# SCH_MyFirstCPU_2022-09-18.net
KiCad netlist of a schematic drawn in EasyEDA
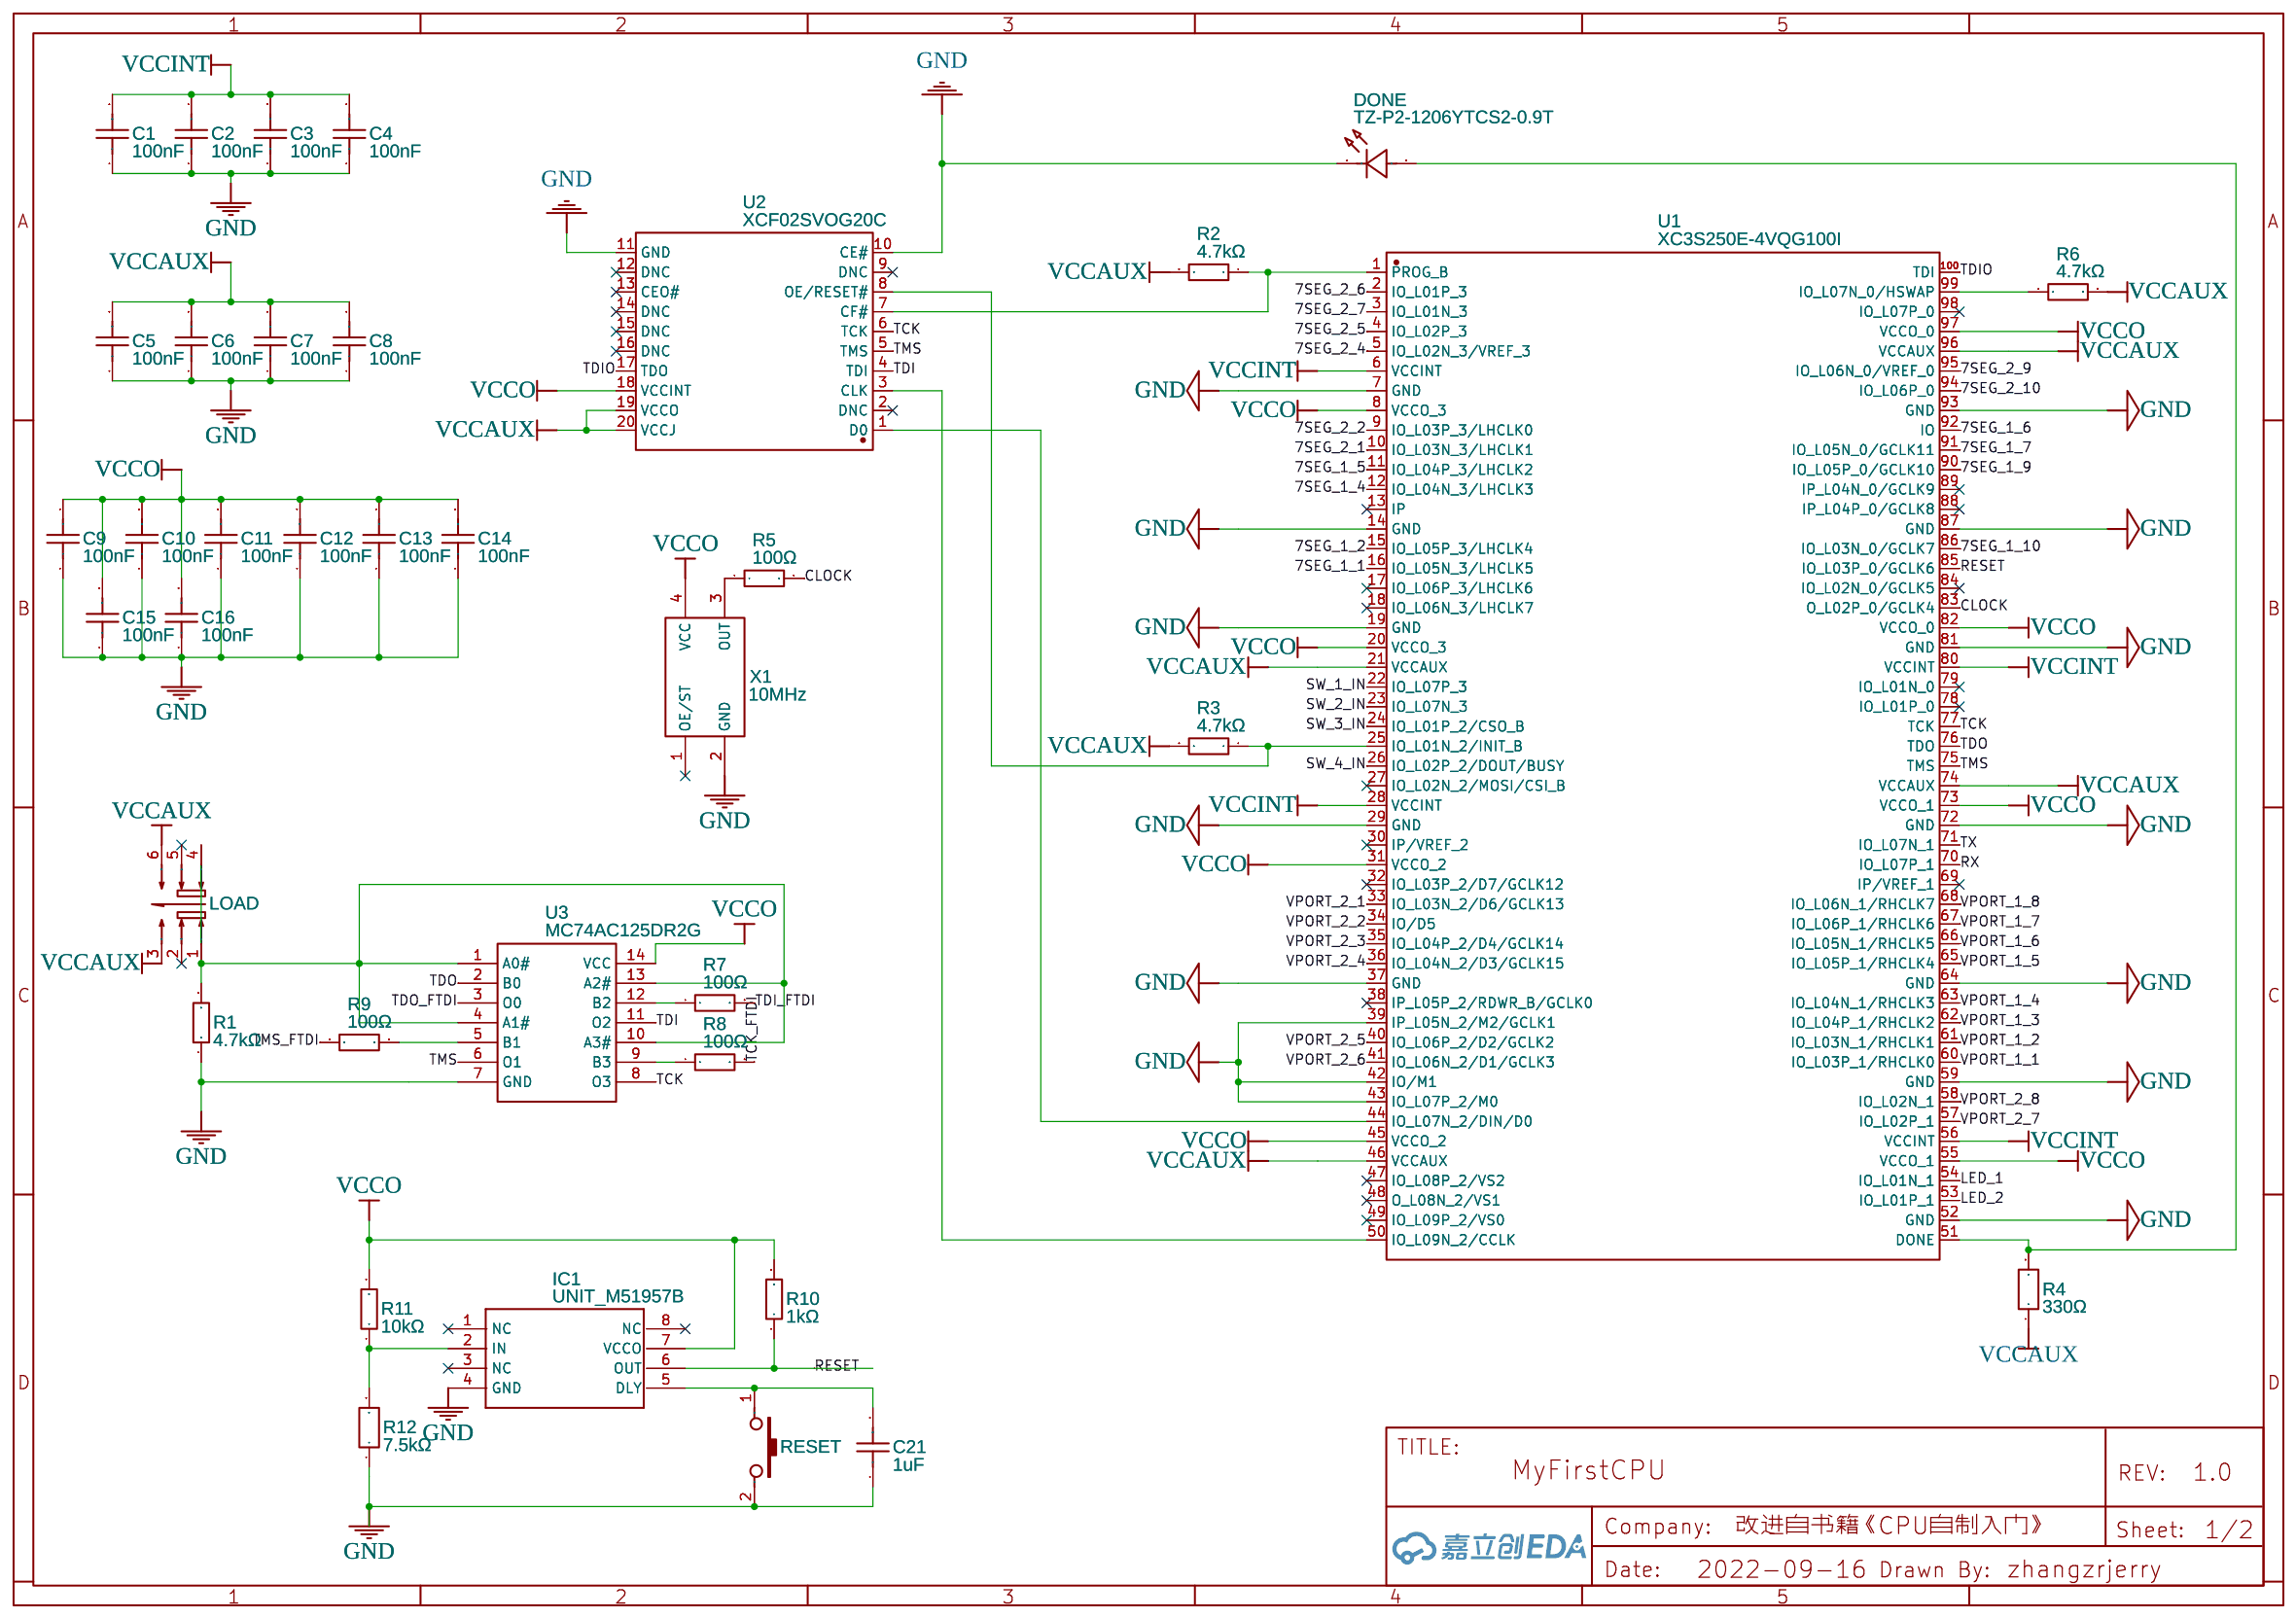
[diagram p0: Sheet_1]
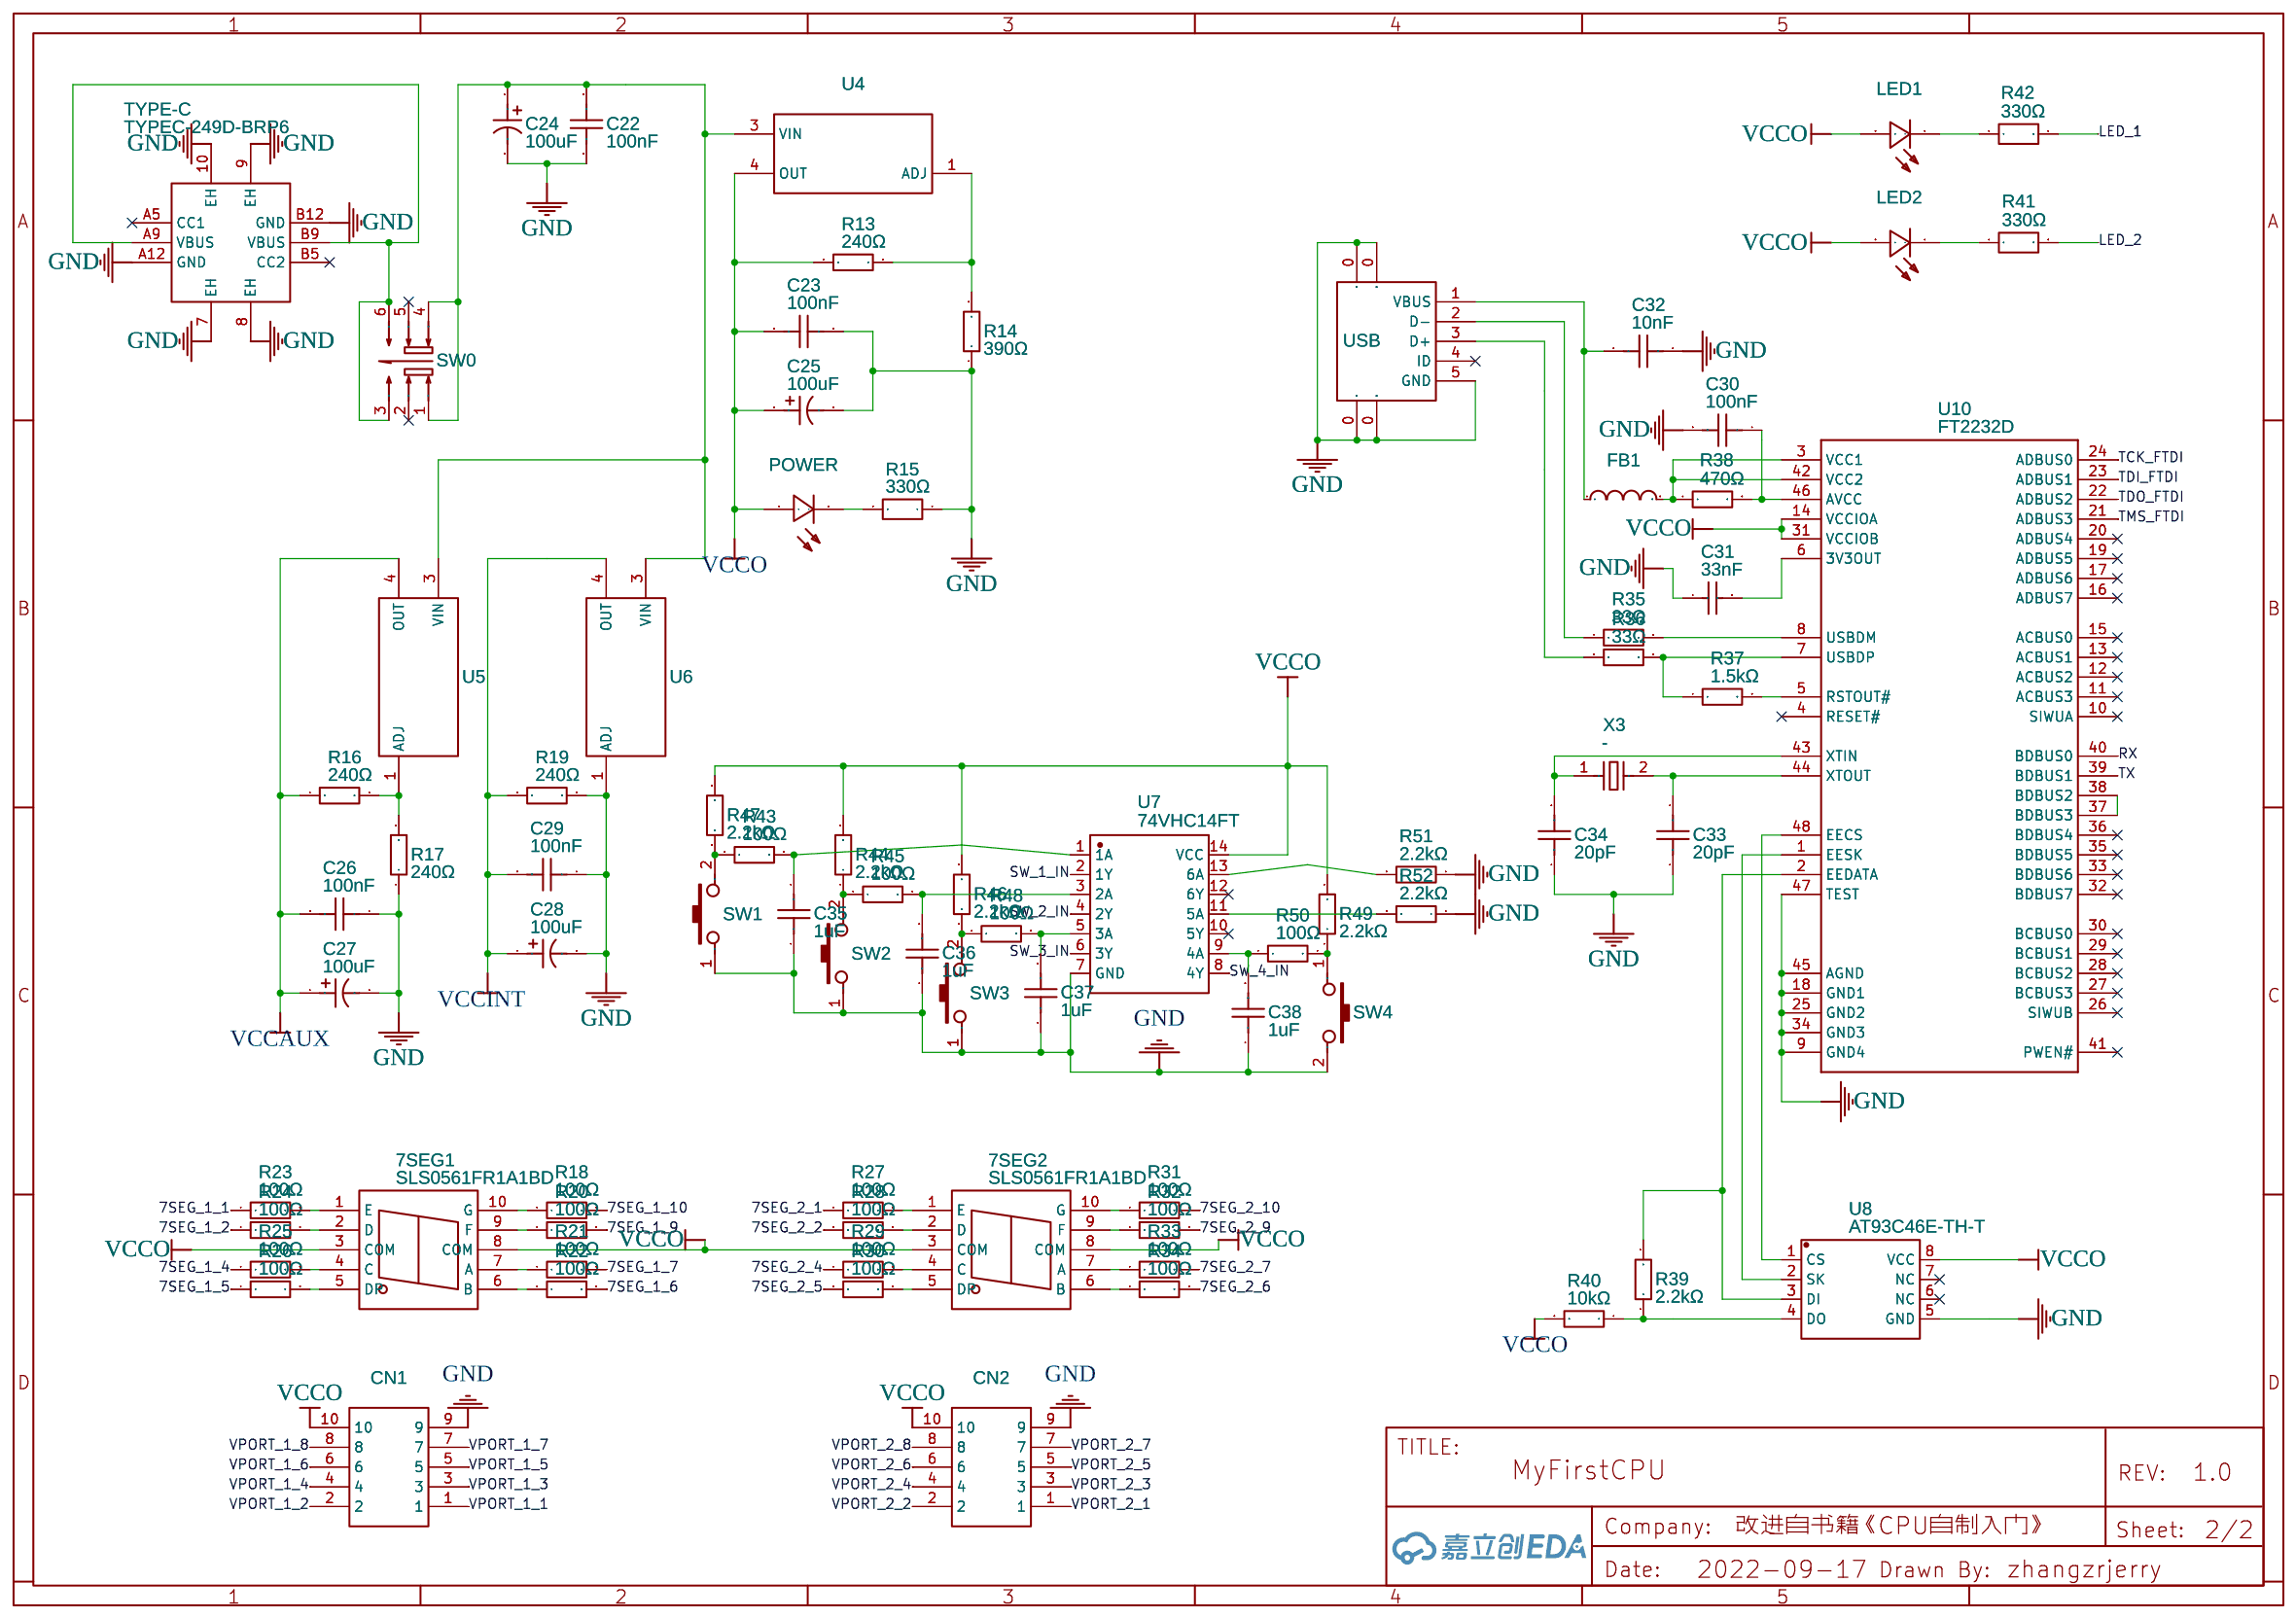
[diagram p1: Sheet_2]

(export (version "E")
  (design (tool "Eeschema 10.0.6"))
  (components
    (comp (ref "C1")
      (value "100nF")
      (fields
        (field (name "BOM_Manufacturer Part") "GRM31MR71H104KA01L")
        (field (name "BOM_Supplier Part") "C469550")
      )
      (libsource (lib "") (part "GRM31MR71H104KA01L"))
    )
    (comp (ref "C2")
      (value "100nF")
      (fields
        (field (name "BOM_Manufacturer Part") "GRM31MR71H104KA01L")
        (field (name "BOM_Supplier Part") "C469550")
      )
      (libsource (lib "") (part "GRM31MR71H104KA01L"))
    )
    (comp (ref "C3")
      (value "100nF")
      (fields
        (field (name "BOM_Manufacturer Part") "GRM31MR71H104KA01L")
        (field (name "BOM_Supplier Part") "C469550")
      )
      (libsource (lib "") (part "GRM31MR71H104KA01L"))
    )
    (comp (ref "C4")
      (value "100nF")
      (fields
        (field (name "BOM_Manufacturer Part") "GRM31MR71H104KA01L")
        (field (name "BOM_Supplier Part") "C469550")
      )
      (libsource (lib "") (part "GRM31MR71H104KA01L"))
    )
    (comp (ref "C5")
      (value "100nF")
      (fields
        (field (name "BOM_Manufacturer Part") "GRM31MR71H104KA01L")
        (field (name "BOM_Supplier Part") "C469550")
      )
      (libsource (lib "") (part "GRM31MR71H104KA01L"))
    )
    (comp (ref "C6")
      (value "100nF")
      (fields
        (field (name "BOM_Manufacturer Part") "GRM31MR71H104KA01L")
        (field (name "BOM_Supplier Part") "C469550")
      )
      (libsource (lib "") (part "GRM31MR71H104KA01L"))
    )
    (comp (ref "C7")
      (value "100nF")
      (fields
        (field (name "BOM_Manufacturer Part") "GRM31MR71H104KA01L")
        (field (name "BOM_Supplier Part") "C469550")
      )
      (libsource (lib "") (part "GRM31MR71H104KA01L"))
    )
    (comp (ref "C8")
      (value "100nF")
      (fields
        (field (name "BOM_Manufacturer Part") "GRM31MR71H104KA01L")
        (field (name "BOM_Supplier Part") "C469550")
      )
      (libsource (lib "") (part "GRM31MR71H104KA01L"))
    )
    (comp (ref "C9")
      (value "100nF")
      (fields
        (field (name "BOM_Manufacturer Part") "GRM31MR71H104KA01L")
        (field (name "BOM_Supplier Part") "C469550")
      )
      (libsource (lib "") (part "GRM31MR71H104KA01L"))
    )
    (comp (ref "C10")
      (value "100nF")
      (fields
        (field (name "BOM_Manufacturer Part") "GRM31MR71H104KA01L")
        (field (name "BOM_Supplier Part") "C469550")
      )
      (libsource (lib "") (part "GRM31MR71H104KA01L"))
    )
    (comp (ref "C11")
      (value "100nF")
      (fields
        (field (name "BOM_Manufacturer Part") "GRM31MR71H104KA01L")
        (field (name "BOM_Supplier Part") "C469550")
      )
      (libsource (lib "") (part "GRM31MR71H104KA01L"))
    )
    (comp (ref "C12")
      (value "100nF")
      (fields
        (field (name "BOM_Manufacturer Part") "GRM31MR71H104KA01L")
        (field (name "BOM_Supplier Part") "C469550")
      )
      (libsource (lib "") (part "GRM31MR71H104KA01L"))
    )
    (comp (ref "C13")
      (value "100nF")
      (fields
        (field (name "BOM_Manufacturer Part") "GRM31MR71H104KA01L")
        (field (name "BOM_Supplier Part") "C469550")
      )
      (libsource (lib "") (part "GRM31MR71H104KA01L"))
    )
    (comp (ref "C14")
      (value "100nF")
      (fields
        (field (name "BOM_Manufacturer Part") "GRM31MR71H104KA01L")
        (field (name "BOM_Supplier Part") "C469550")
      )
      (libsource (lib "") (part "GRM31MR71H104KA01L"))
    )
    (comp (ref "C15")
      (value "100nF")
      (fields
        (field (name "BOM_Manufacturer Part") "GRM31MR71H104KA01L")
        (field (name "BOM_Supplier Part") "C469550")
      )
      (libsource (lib "") (part "GRM31MR71H104KA01L"))
    )
    (comp (ref "C16")
      (value "100nF")
      (fields
        (field (name "BOM_Manufacturer Part") "GRM31MR71H104KA01L")
        (field (name "BOM_Supplier Part") "C469550")
      )
      (libsource (lib "") (part "GRM31MR71H104KA01L"))
    )
    (comp (ref "C21")
      (value "1uF")
      (fields
        (field (name "BOM_Manufacturer Part") "CL31A105KB9LNNC")
        (field (name "BOM_Supplier Part") "C444884")
      )
      (libsource (lib "") (part "CL31A105KB9LNNC"))
    )
    (comp (ref "DONE")
      (value "TZ-P2-1206YTCS2-0.9T")
      (fields (field (name "BOM_Supplier Part") "C779811"))
      (libsource (lib "") (part "TZ-P2-1206YTCS2-0.9T"))
    )
    (comp (ref "IC1") (value "UNIT_M51957B") (libsource (lib "") (part "UNIT_M51957B")))
    (comp (ref "LOAD")
      (value "XKB5858-Z-TP")
      (fields (field (name "BOM_Supplier Part") "C381090"))
      (libsource (lib "") (part "XKB5858-Z-TP"))
    )
    (comp (ref "R1")
      (value "4.7kΩ")
      (fields
        (field (name "BOM_Manufacturer Part") "CR-06JL7---4K7")
        (field (name "BOM_Supplier Part") "C280050")
      )
      (libsource (lib "") (part "CR-06JL7---4K7_1"))
    )
    (comp (ref "R2")
      (value "4.7kΩ")
      (fields
        (field (name "BOM_Manufacturer Part") "CR-06JL7---4K7")
        (field (name "BOM_Supplier Part") "C280050")
      )
      (libsource (lib "") (part "CR-06JL7---4K7"))
    )
    (comp (ref "R3")
      (value "4.7kΩ")
      (fields
        (field (name "BOM_Manufacturer Part") "CR-06JL7---4K7")
        (field (name "BOM_Supplier Part") "C280050")
      )
      (libsource (lib "") (part "CR-06JL7---4K7"))
    )
    (comp (ref "R4")
      (value "330Ω")
      (fields
        (field (name "BOM_Manufacturer Part") "MCR18EZPJ331")
        (field (name "BOM_Supplier Part") "C507456")
      )
      (libsource (lib "") (part "MCR18EZPJ331"))
    )
    (comp (ref "R5")
      (value "100Ω")
      (fields
        (field (name "BOM_Manufacturer Part") "RMC12061001%N")
        (field (name "BOM_Supplier Part") "C325893")
      )
      (libsource (lib "") (part "RMC12061001%N"))
    )
    (comp (ref "R6")
      (value "4.7kΩ")
      (fields
        (field (name "BOM_Manufacturer Part") "CR-06JL7---4K7")
        (field (name "BOM_Supplier Part") "C280050")
      )
      (libsource (lib "") (part "CR-06JL7---4K7_2"))
    )
    (comp (ref "R7")
      (value "100Ω")
      (fields
        (field (name "BOM_Manufacturer Part") "RMC12061001%N")
        (field (name "BOM_Supplier Part") "C325893")
      )
      (libsource (lib "") (part "RMC12061001%N"))
    )
    (comp (ref "R8")
      (value "100Ω")
      (fields
        (field (name "BOM_Manufacturer Part") "RMC12061001%N")
        (field (name "BOM_Supplier Part") "C325893")
      )
      (libsource (lib "") (part "RMC12061001%N"))
    )
    (comp (ref "R9")
      (value "100Ω")
      (fields
        (field (name "BOM_Manufacturer Part") "RMC12061001%N")
        (field (name "BOM_Supplier Part") "C325893")
      )
      (libsource (lib "") (part "RMC12061001%N"))
    )
    (comp (ref "R10")
      (value "1kΩ")
      (fields
        (field (name "BOM_Manufacturer Part") "RMC12061K5%N")
        (field (name "BOM_Supplier Part") "C269755")
      )
      (libsource (lib "") (part "RMC12061K5%N"))
    )
    (comp (ref "R11")
      (value "10kΩ")
      (fields
        (field (name "BOM_Manufacturer Part") "1206W4J0103T5E")
        (field (name "BOM_Supplier Part") "C1489")
      )
      (libsource (lib "") (part "1206W4J0103T5E"))
    )
    (comp (ref "R12")
      (value "7.5kΩ")
      (fields
        (field (name "BOM_Manufacturer Part") "AS0606J0752T5E")
        (field (name "BOM_Supplier Part") "C966034")
      )
      (libsource (lib "") (part "AS0606J0752T5E"))
    )
    (comp (ref "RESET")
      (value "TC")
      (fields
        (field (name "BOM_Manufacturer Part") "TC-3602-4.3-260GKK")
        (field (name "BOM_Supplier Part") "C3012022")
      )
      (libsource (lib "") (part "TC-3602-4.3-260GKK"))
    )
    (comp (ref "U1")
      (value "XC3S250E-4VQG100I")
      (fields (field (name "BOM_Supplier Part") "C2684980"))
      (libsource (lib "") (part "XC3S250E-4VQG100I"))
    )
    (comp (ref "U2")
      (value "XCF02SVOG20C")
      (fields (field (name "BOM_Supplier Part") "C569040"))
      (libsource (lib "") (part "XCF02SVOG20C"))
    )
    (comp (ref "U3")
      (value "MC74AC125DR2G")
      (fields (field (name "BOM_Supplier Part") "C99675"))
      (libsource (lib "") (part "MC74AC125DR2G"))
    )
    (comp (ref "X1")
      (value "10MHz")
      (fields
        (field (name "BOM_Manufacturer Part") "X1G004481000500")
        (field (name "BOM_Supplier Part") "C16850")
      )
      (libsource (lib "") (part "X1G004481000500"))
    )
    (comp (ref "7SEG1")
      (value "SLS0561FR1A1BD")
      (fields (field (name "BOM_Supplier Part") "C226002"))
      (libsource (lib "") (part "SLS0561FR1A1BD"))
    )
    (comp (ref "7SEG2")
      (value "SLS0561FR1A1BD")
      (fields (field (name "BOM_Supplier Part") "C226002"))
      (libsource (lib "") (part "SLS0561FR1A1BD"))
    )
    (comp (ref "C22")
      (value "100nF")
      (fields
        (field (name "BOM_Manufacturer Part") "GRM31MR71H104KA01L")
        (field (name "BOM_Supplier Part") "C469550")
      )
      (libsource (lib "") (part "GRM31MR71H104KA01L_1"))
    )
    (comp (ref "C23")
      (value "100nF")
      (fields
        (field (name "BOM_Manufacturer Part") "GRM31MR71H104KA01L")
        (field (name "BOM_Supplier Part") "C469550")
      )
      (libsource (lib "") (part "GRM31MR71H104KA01L"))
    )
    (comp (ref "C24")
      (value "100uF")
      (fields
        (field (name "BOM_Manufacturer Part") "RVT100UF16V67RV0016")
        (field (name "BOM_Supplier Part") "C2887276")
      )
      (libsource (lib "") (part "RVT100UF16V67RV0016_1"))
    )
    (comp (ref "C25")
      (value "100uF")
      (fields
        (field (name "BOM_Manufacturer Part") "RVT100UF16V67RV0016")
        (field (name "BOM_Supplier Part") "C2887276")
      )
      (libsource (lib "") (part "RVT100UF16V67RV0016"))
    )
    (comp (ref "C26")
      (value "100nF")
      (fields
        (field (name "BOM_Manufacturer Part") "GRM31MR71H104KA01L")
        (field (name "BOM_Supplier Part") "C469550")
      )
      (libsource (lib "") (part "GRM31MR71H104KA01L"))
    )
    (comp (ref "C27")
      (value "100uF")
      (fields
        (field (name "BOM_Manufacturer Part") "RVT100UF16V67RV0016")
        (field (name "BOM_Supplier Part") "C2887276")
      )
      (libsource (lib "") (part "RVT100UF16V67RV0016"))
    )
    (comp (ref "C28")
      (value "100uF")
      (fields
        (field (name "BOM_Manufacturer Part") "RVT100UF16V67RV0016")
        (field (name "BOM_Supplier Part") "C2887276")
      )
      (libsource (lib "") (part "RVT100UF16V67RV0016"))
    )
    (comp (ref "C29")
      (value "100nF")
      (fields
        (field (name "BOM_Manufacturer Part") "GRM31MR71H104KA01L")
        (field (name "BOM_Supplier Part") "C469550")
      )
      (libsource (lib "") (part "GRM31MR71H104KA01L"))
    )
    (comp (ref "C30")
      (value "100nF")
      (fields
        (field (name "BOM_Manufacturer Part") "GRM31MR71H104KA01L")
        (field (name "BOM_Supplier Part") "C469550")
      )
      (libsource (lib "") (part "GRM31MR71H104KA01L"))
    )
    (comp (ref "C31")
      (value "33nF")
      (fields
        (field (name "BOM_Manufacturer Part") "GRM3195C1H333JA01D")
        (field (name "BOM_Supplier Part") "C97930")
      )
      (libsource (lib "") (part "GRM3195C1H333JA01D"))
    )
    (comp (ref "C32")
      (value "10nF")
      (fields
        (field (name "BOM_Manufacturer Part") "TCC1206X7R103K501DTS")
        (field (name "BOM_Supplier Part") "C377058")
      )
      (libsource (lib "") (part "TCC1206X7R103K501DTS"))
    )
    (comp (ref "C33")
      (value "20pF")
      (fields
        (field (name "BOM_Manufacturer Part") "CC1206JRNPO9BN200")
        (field (name "BOM_Supplier Part") "C113883")
      )
      (libsource (lib "") (part "CC1206JRNPO9BN200"))
    )
    (comp (ref "C34")
      (value "20pF")
      (fields
        (field (name "BOM_Manufacturer Part") "CC1206JRNPO9BN200")
        (field (name "BOM_Supplier Part") "C113883")
      )
      (libsource (lib "") (part "CC1206JRNPO9BN200"))
    )
    (comp (ref "C35")
      (value "1uF")
      (fields
        (field (name "BOM_Manufacturer Part") "CL31B105KBHNNNE")
        (field (name "BOM_Supplier Part") "C1848")
      )
      (libsource (lib "") (part "CL31B105KBHNNNE"))
    )
    (comp (ref "C36")
      (value "1uF")
      (fields
        (field (name "BOM_Manufacturer Part") "CL31B105KBHNNNE")
        (field (name "BOM_Supplier Part") "C1848")
      )
      (libsource (lib "") (part "CL31B105KBHNNNE"))
    )
    (comp (ref "C37")
      (value "1uF")
      (fields
        (field (name "BOM_Manufacturer Part") "CL31B105KBHNNNE")
        (field (name "BOM_Supplier Part") "C1848")
      )
      (libsource (lib "") (part "CL31B105KBHNNNE"))
    )
    (comp (ref "C38")
      (value "1uF")
      (fields
        (field (name "BOM_Manufacturer Part") "CL31B105KBHNNNE")
        (field (name "BOM_Supplier Part") "C1848")
      )
      (libsource (lib "") (part "CL31B105KBHNNNE"))
    )
    (comp (ref "CN1")
      (value "Z-231011810106")
      (fields (field (name "BOM_Supplier Part") "C93713"))
      (libsource (lib "") (part "Z-231011810106"))
    )
    (comp (ref "CN2")
      (value "Z-231011810106")
      (fields (field (name "BOM_Supplier Part") "C93713"))
      (libsource (lib "") (part "Z-231011810106"))
    )
    (comp (ref "FB1")
      (value "PZ3216U601-1R5TF")
      (fields (field (name "BOM_Supplier Part") "C370100"))
      (libsource (lib "") (part "PZ3216U601-1R5TF"))
    )
    (comp (ref "LED1")
      (value "E6C1206CWAY1UDA")
      (fields (field (name "BOM_Supplier Part") "C375462"))
      (libsource (lib "") (part "E6C1206CWAY1UDA"))
    )
    (comp (ref "LED2")
      (value "E6C1206CWAY1UDA")
      (fields (field (name "BOM_Supplier Part") "C375462"))
      (libsource (lib "") (part "E6C1206CWAY1UDA"))
    )
    (comp (ref "POWER")
      (value "E6C1206QBAC1UDA")
      (fields (field (name "BOM_Supplier Part") "C375460"))
      (libsource (lib "") (part "E6C1206QBAC1UDA"))
    )
    (comp (ref "R13")
      (value "240Ω")
      (fields
        (field (name "BOM_Manufacturer Part") "1206W4F2400T5E")
        (field (name "BOM_Supplier Part") "C17961")
      )
      (libsource (lib "") (part "1206W4F2400T5E"))
    )
    (comp (ref "R14")
      (value "390Ω")
      (fields
        (field (name "BOM_Manufacturer Part") "1206W4J0391T5E")
        (field (name "BOM_Supplier Part") "C25378")
      )
      (libsource (lib "") (part "1206W4J0391T5E"))
    )
    (comp (ref "R15")
      (value "330Ω")
      (fields
        (field (name "BOM_Manufacturer Part") "MCR18EZPJ331")
        (field (name "BOM_Supplier Part") "C507456")
      )
      (libsource (lib "") (part "MCR18EZPJ331"))
    )
    (comp (ref "R16")
      (value "240Ω")
      (fields
        (field (name "BOM_Manufacturer Part") "1206W4F2400T5E")
        (field (name "BOM_Supplier Part") "C17961")
      )
      (libsource (lib "") (part "1206W4F2400T5E"))
    )
    (comp (ref "R17")
      (value "240Ω")
      (fields
        (field (name "BOM_Manufacturer Part") "1206W4F2400T5E")
        (field (name "BOM_Supplier Part") "C17961")
      )
      (libsource (lib "") (part "1206W4F2400T5E_1"))
    )
    (comp (ref "R18")
      (value "100Ω")
      (fields
        (field (name "BOM_Manufacturer Part") "RMC12061001%N")
        (field (name "BOM_Supplier Part") "C325893")
      )
      (libsource (lib "") (part "RMC12061001%N"))
    )
    (comp (ref "R19")
      (value "240Ω")
      (fields
        (field (name "BOM_Manufacturer Part") "1206W4F2400T5E")
        (field (name "BOM_Supplier Part") "C17961")
      )
      (libsource (lib "") (part "1206W4F2400T5E"))
    )
    (comp (ref "R20")
      (value "100Ω")
      (fields
        (field (name "BOM_Manufacturer Part") "RMC12061001%N")
        (field (name "BOM_Supplier Part") "C325893")
      )
      (libsource (lib "") (part "RMC12061001%N"))
    )
    (comp (ref "R21")
      (value "100Ω")
      (fields
        (field (name "BOM_Manufacturer Part") "RMC12061001%N")
        (field (name "BOM_Supplier Part") "C325893")
      )
      (libsource (lib "") (part "RMC12061001%N"))
    )
    (comp (ref "R22")
      (value "100Ω")
      (fields
        (field (name "BOM_Manufacturer Part") "RMC12061001%N")
        (field (name "BOM_Supplier Part") "C325893")
      )
      (libsource (lib "") (part "RMC12061001%N"))
    )
    (comp (ref "R23")
      (value "100Ω")
      (fields
        (field (name "BOM_Manufacturer Part") "RMC12061001%N")
        (field (name "BOM_Supplier Part") "C325893")
      )
      (libsource (lib "") (part "RMC12061001%N"))
    )
    (comp (ref "R24")
      (value "100Ω")
      (fields
        (field (name "BOM_Manufacturer Part") "RMC12061001%N")
        (field (name "BOM_Supplier Part") "C325893")
      )
      (libsource (lib "") (part "RMC12061001%N"))
    )
    (comp (ref "R25")
      (value "100Ω")
      (fields
        (field (name "BOM_Manufacturer Part") "RMC12061001%N")
        (field (name "BOM_Supplier Part") "C325893")
      )
      (libsource (lib "") (part "RMC12061001%N"))
    )
    (comp (ref "R26")
      (value "100Ω")
      (fields
        (field (name "BOM_Manufacturer Part") "RMC12061001%N")
        (field (name "BOM_Supplier Part") "C325893")
      )
      (libsource (lib "") (part "RMC12061001%N"))
    )
    (comp (ref "R27")
      (value "100Ω")
      (fields
        (field (name "BOM_Manufacturer Part") "RMC12061001%N")
        (field (name "BOM_Supplier Part") "C325893")
      )
      (libsource (lib "") (part "RMC12061001%N"))
    )
    (comp (ref "R28")
      (value "100Ω")
      (fields
        (field (name "BOM_Manufacturer Part") "RMC12061001%N")
        (field (name "BOM_Supplier Part") "C325893")
      )
      (libsource (lib "") (part "RMC12061001%N"))
    )
    (comp (ref "R29")
      (value "100Ω")
      (fields
        (field (name "BOM_Manufacturer Part") "RMC12061001%N")
        (field (name "BOM_Supplier Part") "C325893")
      )
      (libsource (lib "") (part "RMC12061001%N"))
    )
    (comp (ref "R30")
      (value "100Ω")
      (fields
        (field (name "BOM_Manufacturer Part") "RMC12061001%N")
        (field (name "BOM_Supplier Part") "C325893")
      )
      (libsource (lib "") (part "RMC12061001%N"))
    )
    (comp (ref "R31")
      (value "100Ω")
      (fields
        (field (name "BOM_Manufacturer Part") "RMC12061001%N")
        (field (name "BOM_Supplier Part") "C325893")
      )
      (libsource (lib "") (part "RMC12061001%N"))
    )
    (comp (ref "R32")
      (value "100Ω")
      (fields
        (field (name "BOM_Manufacturer Part") "RMC12061001%N")
        (field (name "BOM_Supplier Part") "C325893")
      )
      (libsource (lib "") (part "RMC12061001%N"))
    )
    (comp (ref "R33")
      (value "100Ω")
      (fields
        (field (name "BOM_Manufacturer Part") "RMC12061001%N")
        (field (name "BOM_Supplier Part") "C325893")
      )
      (libsource (lib "") (part "RMC12061001%N"))
    )
    (comp (ref "R34")
      (value "100Ω")
      (fields
        (field (name "BOM_Manufacturer Part") "RMC12061001%N")
        (field (name "BOM_Supplier Part") "C325893")
      )
      (libsource (lib "") (part "RMC12061001%N"))
    )
    (comp (ref "R35")
      (value "33Ω")
      (fields
        (field (name "BOM_Manufacturer Part") "1206W4J0330T5E")
        (field (name "BOM_Supplier Part") "C25375")
      )
      (libsource (lib "") (part "1206W4J0330T5E"))
    )
    (comp (ref "R36")
      (value "33Ω")
      (fields
        (field (name "BOM_Manufacturer Part") "1206W4J0330T5E")
        (field (name "BOM_Supplier Part") "C25375")
      )
      (libsource (lib "") (part "1206W4J0330T5E"))
    )
    (comp (ref "R37")
      (value "1.5kΩ")
      (fields
        (field (name "BOM_Manufacturer Part") "1206W4F1501T5E")
        (field (name "BOM_Supplier Part") "C26030")
      )
      (libsource (lib "") (part "1206W4F1501T5E"))
    )
    (comp (ref "R38")
      (value "470Ω")
      (fields
        (field (name "BOM_Manufacturer Part") "RS-06K471JT")
        (field (name "BOM_Supplier Part") "C118071")
      )
      (libsource (lib "") (part "RS-06K471JT"))
    )
    (comp (ref "R39")
      (value "2.2kΩ")
      (fields
        (field (name "BOM_Manufacturer Part") "1206W4J0222T5E")
        (field (name "BOM_Supplier Part") "C26038")
      )
      (libsource (lib "") (part "1206W4J0222T5E"))
    )
    (comp (ref "R40")
      (value "10kΩ")
      (fields
        (field (name "BOM_Manufacturer Part") "1206W4J0103T5E")
        (field (name "BOM_Supplier Part") "C1489")
      )
      (libsource (lib "") (part "1206W4J0103T5E"))
    )
    (comp (ref "R41")
      (value "330Ω")
      (fields
        (field (name "BOM_Manufacturer Part") "MCR18EZPJ331")
        (field (name "BOM_Supplier Part") "C507456")
      )
      (libsource (lib "") (part "MCR18EZPJ331_1"))
    )
    (comp (ref "R42")
      (value "330Ω")
      (fields
        (field (name "BOM_Manufacturer Part") "MCR18EZPJ331")
        (field (name "BOM_Supplier Part") "C507456")
      )
      (libsource (lib "") (part "MCR18EZPJ331_1"))
    )
    (comp (ref "R43")
      (value "100Ω")
      (fields
        (field (name "BOM_Manufacturer Part") "RMC12061001%N")
        (field (name "BOM_Supplier Part") "C325893")
      )
      (libsource (lib "") (part "RMC12061001%N"))
    )
    (comp (ref "R44")
      (value "2.2kΩ")
      (fields
        (field (name "BOM_Manufacturer Part") "1206W4J0222T5E")
        (field (name "BOM_Supplier Part") "C26038")
      )
      (libsource (lib "") (part "1206W4J0222T5E"))
    )
    (comp (ref "R45")
      (value "100Ω")
      (fields
        (field (name "BOM_Manufacturer Part") "RMC12061001%N")
        (field (name "BOM_Supplier Part") "C325893")
      )
      (libsource (lib "") (part "RMC12061001%N"))
    )
    (comp (ref "R46")
      (value "2.2kΩ")
      (fields
        (field (name "BOM_Manufacturer Part") "1206W4J0222T5E")
        (field (name "BOM_Supplier Part") "C26038")
      )
      (libsource (lib "") (part "1206W4J0222T5E"))
    )
    (comp (ref "R47")
      (value "2.2kΩ")
      (fields
        (field (name "BOM_Manufacturer Part") "1206W4J0222T5E")
        (field (name "BOM_Supplier Part") "C26038")
      )
      (libsource (lib "") (part "1206W4J0222T5E"))
    )
    (comp (ref "R48")
      (value "100Ω")
      (fields
        (field (name "BOM_Manufacturer Part") "RMC12061001%N")
        (field (name "BOM_Supplier Part") "C325893")
      )
      (libsource (lib "") (part "RMC12061001%N"))
    )
    (comp (ref "R49")
      (value "2.2kΩ")
      (fields
        (field (name "BOM_Manufacturer Part") "1206W4J0222T5E")
        (field (name "BOM_Supplier Part") "C26038")
      )
      (libsource (lib "") (part "1206W4J0222T5E"))
    )
    (comp (ref "R50")
      (value "100Ω")
      (fields
        (field (name "BOM_Manufacturer Part") "RMC12061001%N")
        (field (name "BOM_Supplier Part") "C325893")
      )
      (libsource (lib "") (part "RMC12061001%N"))
    )
    (comp (ref "R51")
      (value "2.2kΩ")
      (fields
        (field (name "BOM_Manufacturer Part") "1206W4J0222T5E")
        (field (name "BOM_Supplier Part") "C26038")
      )
      (libsource (lib "") (part "1206W4J0222T5E_1"))
    )
    (comp (ref "R52")
      (value "2.2kΩ")
      (fields
        (field (name "BOM_Manufacturer Part") "1206W4J0222T5E")
        (field (name "BOM_Supplier Part") "C26038")
      )
      (libsource (lib "") (part "1206W4J0222T5E_1"))
    )
    (comp (ref "SW0")
      (value "XKB5858-Z-TP")
      (fields (field (name "BOM_Supplier Part") "C381090"))
      (libsource (lib "") (part "XKB5858-Z-TP"))
    )
    (comp (ref "SW1")
      (value "TC")
      (fields
        (field (name "BOM_Manufacturer Part") "TC-3602-4.3-260GKK")
        (field (name "BOM_Supplier Part") "C3012022")
      )
      (libsource (lib "") (part "TC-3602-4.3-260GKK_1"))
    )
    (comp (ref "SW2")
      (value "TC")
      (fields
        (field (name "BOM_Manufacturer Part") "TC-3602-4.3-260GKK")
        (field (name "BOM_Supplier Part") "C3012022")
      )
      (libsource (lib "") (part "TC-3602-4.3-260GKK_1"))
    )
    (comp (ref "SW3")
      (value "TC")
      (fields
        (field (name "BOM_Manufacturer Part") "TC-3602-4.3-260GKK")
        (field (name "BOM_Supplier Part") "C3012022")
      )
      (libsource (lib "") (part "TC-3602-4.3-260GKK_1"))
    )
    (comp (ref "SW4")
      (value "TC")
      (fields
        (field (name "BOM_Manufacturer Part") "TC-3602-4.3-260GKK")
        (field (name "BOM_Supplier Part") "C3012022")
      )
      (libsource (lib "") (part "TC-3602-4.3-260GKK"))
    )
    (comp (ref "TYPE-C")
      (value "TYPEC-249D-BRP6")
      (fields (field (name "BOM_Supplier Part") "C2895023"))
      (libsource (lib "") (part "TYPEC-249D-BRP6"))
    )
    (comp (ref "U4")
      (value "LM317AG-TN3-R")
      (fields (field (name "BOM_Supplier Part") "C75510"))
      (libsource (lib "") (part "LM317AG-TN3-R"))
    )
    (comp (ref "U5")
      (value "LM317AG-TN3-R")
      (fields (field (name "BOM_Supplier Part") "C75510"))
      (libsource (lib "") (part "LM317AG-TN3-R_1"))
    )
    (comp (ref "U6")
      (value "LM317AG-TN3-R")
      (fields (field (name "BOM_Supplier Part") "C75510"))
      (libsource (lib "") (part "LM317AG-TN3-R_1"))
    )
    (comp (ref "U7")
      (value "74VHC14FT")
      (fields (field (name "BOM_Supplier Part") "C80863"))
      (libsource (lib "") (part "74VHC14FT"))
    )
    (comp (ref "U8")
      (value "AT93C46E-TH-T")
      (fields (field (name "BOM_Supplier Part") "C184789"))
      (libsource (lib "") (part "AT93C46E-TH-T"))
    )
    (comp (ref "U10")
      (value "FT2232D")
      (fields (field (name "BOM_Supplier Part") "C8938"))
      (libsource (lib "") (part "FT2232D"))
    )
    (comp (ref "USB")
      (value "U254-051N-4BH83-F1B")
      (fields (field (name "BOM_Supplier Part") "C319169"))
      (libsource (lib "") (part "U254-051N-4BH83-F1B"))
    )
    (comp (ref "X3")
      (value "-")
      (fields
        (field (name "BOM_Manufacturer Part") "TAXM6M2IHDBET2T")
        (field (name "BOM_Supplier Part") "C696838")
      )
      (libsource (lib "") (part "TAXM6M2IHDBET2T"))
    )
  )
  (nets
    (net (code "1") (name "7SEG_1_1") (class "Default")
      (node (ref "R23") (pin "1") (pinfunction "1_1") (pintype "unspecified"))
      (node (ref "U1") (pin "16") (pinfunction "IO_L05N_3/LHCLK5_16") (pintype "unspecified"))
    )
    (net (code "2") (name "7SEG_1_2") (class "Default")
      (node (ref "R24") (pin "1") (pinfunction "1_1") (pintype "unspecified"))
      (node (ref "U1") (pin "15") (pinfunction "IO_L05P_3/LHCLK4_15") (pintype "unspecified"))
    )
    (net (code "3") (name "7SEG_1_4") (class "Default")
      (node (ref "R25") (pin "1") (pinfunction "1_1") (pintype "unspecified"))
      (node (ref "U1") (pin "12") (pinfunction "IO_L04N_3/LHCLK3_12") (pintype "unspecified"))
    )
    (net (code "4") (name "7SEG_1_5") (class "Default")
      (node (ref "R26") (pin "1") (pinfunction "1_1") (pintype "unspecified"))
      (node (ref "U1") (pin "11") (pinfunction "IO_L04P_3/LHCLK2_11") (pintype "unspecified"))
    )
    (net (code "5") (name "7SEG_1_6") (class "Default")
      (node (ref "R22") (pin "2") (pinfunction "2_2") (pintype "unspecified"))
      (node (ref "U1") (pin "92") (pinfunction "IO_92") (pintype "unspecified"))
    )
    (net (code "6") (name "7SEG_1_7") (class "Default")
      (node (ref "R21") (pin "2") (pinfunction "2_2") (pintype "unspecified"))
      (node (ref "U1") (pin "91") (pinfunction "IO_L05N_0/GCLK11_91") (pintype "unspecified"))
    )
    (net (code "7") (name "7SEG_1_9") (class "Default")
      (node (ref "R20") (pin "2") (pinfunction "2_2") (pintype "unspecified"))
      (node (ref "U1") (pin "90") (pinfunction "IO_L05P_0/GCLK10_90") (pintype "unspecified"))
    )
    (net (code "8") (name "7SEG_1_10") (class "Default")
      (node (ref "R18") (pin "2") (pinfunction "2_2") (pintype "unspecified"))
      (node (ref "U1") (pin "86") (pinfunction "IO_L03N_0/GCLK7_86") (pintype "unspecified"))
    )
    (net (code "9") (name "7SEG_2_1") (class "Default")
      (node (ref "R27") (pin "1") (pinfunction "1_1") (pintype "unspecified"))
      (node (ref "U1") (pin "10") (pinfunction "IO_L03N_3/LHCLK1_10") (pintype "unspecified"))
    )
    (net (code "10") (name "7SEG_2_2") (class "Default")
      (node (ref "R28") (pin "1") (pinfunction "1_1") (pintype "unspecified"))
      (node (ref "U1") (pin "9") (pinfunction "IO_L03P_3/LHCLK0_9") (pintype "unspecified"))
    )
    (net (code "11") (name "7SEG_2_4") (class "Default")
      (node (ref "R29") (pin "1") (pinfunction "1_1") (pintype "unspecified"))
      (node (ref "U1") (pin "5") (pinfunction "IO_L02N_3/VREF_3_5") (pintype "unspecified"))
    )
    (net (code "12") (name "7SEG_2_5") (class "Default")
      (node (ref "R30") (pin "1") (pinfunction "1_1") (pintype "unspecified"))
      (node (ref "U1") (pin "4") (pinfunction "IO_L02P_3_4") (pintype "unspecified"))
    )
    (net (code "13") (name "7SEG_2_6") (class "Default")
      (node (ref "R34") (pin "2") (pinfunction "2_2") (pintype "unspecified"))
      (node (ref "U1") (pin "2") (pinfunction "IO_L01P_3_2") (pintype "unspecified"))
    )
    (net (code "14") (name "7SEG_2_7") (class "Default")
      (node (ref "R33") (pin "2") (pinfunction "2_2") (pintype "unspecified"))
      (node (ref "U1") (pin "3") (pinfunction "IO_L01N_3_3") (pintype "unspecified"))
    )
    (net (code "15") (name "7SEG_2_9") (class "Default")
      (node (ref "R32") (pin "2") (pinfunction "2_2") (pintype "unspecified"))
      (node (ref "U1") (pin "95") (pinfunction "IO_L06N_0/VREF_0_95") (pintype "unspecified"))
    )
    (net (code "16") (name "7SEG_2_10") (class "Default")
      (node (ref "R31") (pin "2") (pinfunction "2_2") (pintype "unspecified"))
      (node (ref "U1") (pin "94") (pinfunction "IO_L06P_0_94") (pintype "unspecified"))
    )
    (net (code "17") (name "CLOCK") (class "Default")
      (node (ref "R5") (pin "2") (pinfunction "2_2") (pintype "unspecified"))
      (node (ref "U1") (pin "83") (pinfunction "O_L02P_0/GCLK4_83") (pintype "unspecified"))
    )
    (net (code "18") (name "GND") (class "Default")
      (node (ref "C1") (pin "1") (pinfunction "1_1") (pintype "unspecified"))
      (node (ref "C10") (pin "1") (pinfunction "1_1") (pintype "unspecified"))
      (node (ref "C11") (pin "1") (pinfunction "1_1") (pintype "unspecified"))
      (node (ref "C12") (pin "1") (pinfunction "1_1") (pintype "unspecified"))
      (node (ref "C13") (pin "1") (pinfunction "1_1") (pintype "unspecified"))
      (node (ref "C14") (pin "1") (pinfunction "1_1") (pintype "unspecified"))
      (node (ref "C15") (pin "1") (pinfunction "1_1") (pintype "unspecified"))
      (node (ref "C16") (pin "1") (pinfunction "1_1") (pintype "unspecified"))
      (node (ref "C2") (pin "1") (pinfunction "1_1") (pintype "unspecified"))
      (node (ref "C21") (pin "1") (pinfunction "1_1") (pintype "unspecified"))
      (node (ref "C22") (pin "1") (pinfunction "1_1") (pintype "unspecified"))
      (node (ref "C23") (pin "1") (pinfunction "1_1") (pintype "unspecified"))
      (node (ref "C24") (pin "2") (pinfunction "2_2") (pintype "input"))
      (node (ref "C25") (pin "2") (pinfunction "2_2") (pintype "input"))
      (node (ref "C26") (pin "1") (pinfunction "1_1") (pintype "unspecified"))
      (node (ref "C27") (pin "2") (pinfunction "2_2") (pintype "input"))
      (node (ref "C28") (pin "2") (pinfunction "2_2") (pintype "input"))
      (node (ref "C29") (pin "1") (pinfunction "1_1") (pintype "unspecified"))
      (node (ref "C3") (pin "1") (pinfunction "1_1") (pintype "unspecified"))
      (node (ref "C30") (pin "2") (pinfunction "2_2") (pintype "unspecified"))
      (node (ref "C31") (pin "1") (pinfunction "1_1") (pintype "input"))
      (node (ref "C32") (pin "1") (pinfunction "1_1") (pintype "unspecified"))
      (node (ref "C33") (pin "1") (pinfunction "1_1") (pintype "unspecified"))
      (node (ref "C34") (pin "1") (pinfunction "1_1") (pintype "unspecified"))
      (node (ref "C35") (pin "1") (pinfunction "1_1") (pintype "unspecified"))
      (node (ref "C36") (pin "1") (pinfunction "1_1") (pintype "unspecified"))
      (node (ref "C37") (pin "1") (pinfunction "1_1") (pintype "unspecified"))
      (node (ref "C38") (pin "1") (pinfunction "1_1") (pintype "unspecified"))
      (node (ref "C4") (pin "1") (pinfunction "1_1") (pintype "unspecified"))
      (node (ref "C5") (pin "1") (pinfunction "1_1") (pintype "unspecified"))
      (node (ref "C6") (pin "1") (pinfunction "1_1") (pintype "unspecified"))
      (node (ref "C7") (pin "1") (pinfunction "1_1") (pintype "unspecified"))
      (node (ref "C8") (pin "1") (pinfunction "1_1") (pintype "unspecified"))
      (node (ref "C9") (pin "1") (pinfunction "1_1") (pintype "unspecified"))
      (node (ref "CN1") (pin "9") (pinfunction "9_9") (pintype "unspecified"))
      (node (ref "CN2") (pin "9") (pinfunction "9_9") (pintype "unspecified"))
      (node (ref "DONE") (pin "1") (pinfunction "K_1") (pintype "unspecified"))
      (node (ref "IC1") (pin "4") (pinfunction "GND_4") (pintype "bidirectional"))
      (node (ref "R1") (pin "1") (pinfunction "1_1") (pintype "unspecified"))
      (node (ref "R12") (pin "1") (pinfunction "1_1") (pintype "unspecified"))
      (node (ref "R14") (pin "1") (pinfunction "1_1") (pintype "input"))
      (node (ref "R15") (pin "1") (pinfunction "1_1") (pintype "unspecified"))
      (node (ref "R17") (pin "1") (pinfunction "1_1") (pintype "input"))
      (node (ref "R19") (pin "2") (pinfunction "2_2") (pintype "input"))
      (node (ref "R51") (pin "1") (pinfunction "1_1") (pintype "input"))
      (node (ref "R52") (pin "1") (pinfunction "1_1") (pintype "input"))
      (node (ref "RESET") (pin "2") (pinfunction "2_2") (pintype "input"))
      (node (ref "SW1") (pin "1") (pinfunction "1_1") (pintype "input"))
      (node (ref "SW2") (pin "1") (pinfunction "1_1") (pintype "input"))
      (node (ref "SW3") (pin "1") (pinfunction "1_1") (pintype "input"))
      (node (ref "SW4") (pin "2") (pinfunction "2_2") (pintype "input"))
      (node (ref "TYPE-C") (pin "10") (pinfunction "EH_10") (pintype "unspecified"))
      (node (ref "TYPE-C") (pin "7") (pinfunction "EH_7") (pintype "unspecified"))
      (node (ref "TYPE-C") (pin "8") (pinfunction "EH_8") (pintype "unspecified"))
      (node (ref "TYPE-C") (pin "9") (pinfunction "EH_9") (pintype "unspecified"))
      (node (ref "TYPE-C") (pin "A12") (pinfunction "GND_A12") (pintype "unspecified"))
      (node (ref "TYPE-C") (pin "B12") (pinfunction "GND_B12") (pintype "unspecified"))
      (node (ref "U1") (pin "14") (pinfunction "GND_14") (pintype "unspecified"))
      (node (ref "U1") (pin "19") (pinfunction "GND_19") (pintype "unspecified"))
      (node (ref "U1") (pin "29") (pinfunction "GND_29") (pintype "unspecified"))
      (node (ref "U1") (pin "37") (pinfunction "GND_37") (pintype "unspecified"))
      (node (ref "U1") (pin "39") (pinfunction "IP_L05N_2/M2/GCLK1_39") (pintype "unspecified"))
      (node (ref "U1") (pin "42") (pinfunction "IO/M1_42") (pintype "unspecified"))
      (node (ref "U1") (pin "43") (pinfunction "IO_L07P_2/M0_43") (pintype "unspecified"))
      (node (ref "U1") (pin "52") (pinfunction "GND_52") (pintype "unspecified"))
      (node (ref "U1") (pin "59") (pinfunction "GND_59") (pintype "unspecified"))
      (node (ref "U1") (pin "64") (pinfunction "GND_64") (pintype "unspecified"))
      (node (ref "U1") (pin "7") (pinfunction "GND_7") (pintype "unspecified"))
      (node (ref "U1") (pin "72") (pinfunction "GND_72") (pintype "unspecified"))
      (node (ref "U1") (pin "81") (pinfunction "GND_81") (pintype "unspecified"))
      (node (ref "U1") (pin "87") (pinfunction "GND_87") (pintype "unspecified"))
      (node (ref "U1") (pin "93") (pinfunction "GND_93") (pintype "unspecified"))
      (node (ref "U10") (pin "18") (pinfunction "GND1_18") (pintype "passive"))
      (node (ref "U10") (pin "25") (pinfunction "GND2_25") (pintype "passive"))
      (node (ref "U10") (pin "34") (pinfunction "GND3_34") (pintype "passive"))
      (node (ref "U10") (pin "45") (pinfunction "AGND_45") (pintype "passive"))
      (node (ref "U10") (pin "47") (pinfunction "TEST_47") (pintype "input"))
      (node (ref "U10") (pin "9") (pinfunction "GND4_9") (pintype "unspecified"))
      (node (ref "U2") (pin "10") (pinfunction "CE#_10") (pintype "unspecified"))
      (node (ref "U2") (pin "11") (pinfunction "GND_11") (pintype "unspecified"))
      (node (ref "U3") (pin "7") (pinfunction "GND_7") (pintype "unspecified"))
      (node (ref "U6") (pin "1") (pinfunction "ADJ_1") (pintype "unspecified"))
      (node (ref "U7") (pin "7") (pinfunction "GND_7") (pintype "unspecified"))
      (node (ref "U8") (pin "5") (pinfunction "GND_5") (pintype "unspecified"))
      (node (ref "USB") (pin "0") (pinfunction "0_0") (pintype "unspecified"))
      (node (ref "USB") (pin "5") (pinfunction "GND_5") (pintype "unspecified"))
      (node (ref "X1") (pin "2") (pinfunction "GND_2") (pintype "unspecified"))
    )
    (net (code "19") (name "LED_1") (class "Default")
      (node (ref "R42") (pin "2") (pinfunction "2_2") (pintype "unspecified"))
      (node (ref "U1") (pin "54") (pinfunction "IO_L01N_1_54") (pintype "unspecified"))
    )
    (net (code "20") (name "LED_2") (class "Default")
      (node (ref "R41") (pin "2") (pinfunction "2_2") (pintype "unspecified"))
      (node (ref "U1") (pin "53") (pinfunction "IO_L01P_1_53") (pintype "unspecified"))
    )
    (net (code "21") (name "Net-(7SEG1-A)") (class "Default")
      (node (ref "7SEG1") (pin "7") (pinfunction "A_7") (pintype "unspecified"))
      (node (ref "R21") (pin "1") (pinfunction "1_1") (pintype "unspecified"))
    )
    (net (code "22") (name "Net-(7SEG1-B)") (class "Default")
      (node (ref "7SEG1") (pin "6") (pinfunction "B_6") (pintype "unspecified"))
      (node (ref "R22") (pin "1") (pinfunction "1_1") (pintype "unspecified"))
    )
    (net (code "23") (name "Net-(7SEG1-C)") (class "Default")
      (node (ref "7SEG1") (pin "4") (pinfunction "C_4") (pintype "unspecified"))
      (node (ref "R25") (pin "2") (pinfunction "2_2") (pintype "unspecified"))
    )
    (net (code "24") (name "Net-(7SEG1-D)") (class "Default")
      (node (ref "7SEG1") (pin "2") (pinfunction "D_2") (pintype "unspecified"))
      (node (ref "R24") (pin "2") (pinfunction "2_2") (pintype "unspecified"))
    )
    (net (code "25") (name "Net-(7SEG1-DP)") (class "Default")
      (node (ref "7SEG1") (pin "5") (pinfunction "DP_5") (pintype "unspecified"))
      (node (ref "R26") (pin "2") (pinfunction "2_2") (pintype "unspecified"))
    )
    (net (code "26") (name "Net-(7SEG1-E)") (class "Default")
      (node (ref "7SEG1") (pin "1") (pinfunction "E_1") (pintype "unspecified"))
      (node (ref "R23") (pin "2") (pinfunction "2_2") (pintype "unspecified"))
    )
    (net (code "27") (name "Net-(7SEG1-F)") (class "Default")
      (node (ref "7SEG1") (pin "9") (pinfunction "F_9") (pintype "unspecified"))
      (node (ref "R20") (pin "1") (pinfunction "1_1") (pintype "unspecified"))
    )
    (net (code "28") (name "Net-(7SEG1-G)") (class "Default")
      (node (ref "7SEG1") (pin "10") (pinfunction "G_10") (pintype "unspecified"))
      (node (ref "R18") (pin "1") (pinfunction "1_1") (pintype "unspecified"))
    )
    (net (code "29") (name "Net-(7SEG2-A)") (class "Default")
      (node (ref "7SEG2") (pin "7") (pinfunction "A_7") (pintype "unspecified"))
      (node (ref "R33") (pin "1") (pinfunction "1_1") (pintype "unspecified"))
    )
    (net (code "30") (name "Net-(7SEG2-B)") (class "Default")
      (node (ref "7SEG2") (pin "6") (pinfunction "B_6") (pintype "unspecified"))
      (node (ref "R34") (pin "1") (pinfunction "1_1") (pintype "unspecified"))
    )
    (net (code "31") (name "Net-(7SEG2-C)") (class "Default")
      (node (ref "7SEG2") (pin "4") (pinfunction "C_4") (pintype "unspecified"))
      (node (ref "R29") (pin "2") (pinfunction "2_2") (pintype "unspecified"))
    )
    (net (code "32") (name "Net-(7SEG2-D)") (class "Default")
      (node (ref "7SEG2") (pin "2") (pinfunction "D_2") (pintype "unspecified"))
      (node (ref "R28") (pin "2") (pinfunction "2_2") (pintype "unspecified"))
    )
    (net (code "33") (name "Net-(7SEG2-DP)") (class "Default")
      (node (ref "7SEG2") (pin "5") (pinfunction "DP_5") (pintype "unspecified"))
      (node (ref "R30") (pin "2") (pinfunction "2_2") (pintype "unspecified"))
    )
    (net (code "34") (name "Net-(7SEG2-E)") (class "Default")
      (node (ref "7SEG2") (pin "1") (pinfunction "E_1") (pintype "unspecified"))
      (node (ref "R27") (pin "2") (pinfunction "2_2") (pintype "unspecified"))
    )
    (net (code "35") (name "Net-(7SEG2-F)") (class "Default")
      (node (ref "7SEG2") (pin "9") (pinfunction "F_9") (pintype "unspecified"))
      (node (ref "R32") (pin "1") (pinfunction "1_1") (pintype "unspecified"))
    )
    (net (code "36") (name "Net-(7SEG2-G)") (class "Default")
      (node (ref "7SEG2") (pin "10") (pinfunction "G_10") (pintype "unspecified"))
      (node (ref "R31") (pin "1") (pinfunction "1_1") (pintype "unspecified"))
    )
    (net (code "37") (name "Net-(DONE-A)") (class "Default")
      (node (ref "DONE") (pin "2") (pinfunction "A_2") (pintype "unspecified"))
      (node (ref "R4") (pin "2") (pinfunction "2_2") (pintype "unspecified"))
      (node (ref "U1") (pin "51") (pinfunction "DONE_51") (pintype "unspecified"))
    )
    (net (code "38") (name "Net-(IC1-DLY)") (class "Default")
      (node (ref "C21") (pin "2") (pinfunction "2_2") (pintype "unspecified"))
      (node (ref "IC1") (pin "5") (pinfunction "DLY_5") (pintype "bidirectional"))
      (node (ref "RESET") (pin "1") (pinfunction "1_1") (pintype "input"))
    )
    (net (code "39") (name "Net-(IC1-IN)") (class "Default")
      (node (ref "IC1") (pin "2") (pinfunction "IN_2") (pintype "bidirectional"))
      (node (ref "R11") (pin "1") (pinfunction "1_1") (pintype "input"))
      (node (ref "R12") (pin "2") (pinfunction "2_2") (pintype "unspecified"))
    )
    (net (code "40") (name "Net-(LED1--)") (class "Default")
      (node (ref "LED1") (pin "1") (pinfunction "-_1") (pintype "unspecified"))
      (node (ref "R42") (pin "1") (pinfunction "1_1") (pintype "unspecified"))
    )
    (net (code "41") (name "Net-(LED2--)") (class "Default")
      (node (ref "LED2") (pin "1") (pinfunction "-_1") (pintype "unspecified"))
      (node (ref "R41") (pin "1") (pinfunction "1_1") (pintype "unspecified"))
    )
    (net (code "42") (name "Net-(POWER--)") (class "Default")
      (node (ref "POWER") (pin "2") (pinfunction "-_2") (pintype "unspecified"))
      (node (ref "R15") (pin "2") (pinfunction "2_2") (pintype "unspecified"))
    )
    (net (code "43") (name "Net-(R43-Pad1)") (class "Default")
      (node (ref "R43") (pin "1") (pinfunction "1_1") (pintype "unspecified"))
      (node (ref "R47") (pin "1") (pinfunction "1_1") (pintype "input"))
      (node (ref "SW1") (pin "2") (pinfunction "2_2") (pintype "input"))
    )
    (net (code "44") (name "Net-(R44-Pad1)") (class "Default")
      (node (ref "R44") (pin "1") (pinfunction "1_1") (pintype "input"))
      (node (ref "R45") (pin "1") (pinfunction "1_1") (pintype "unspecified"))
      (node (ref "SW2") (pin "2") (pinfunction "2_2") (pintype "input"))
    )
    (net (code "45") (name "Net-(R46-Pad1)") (class "Default")
      (node (ref "R46") (pin "1") (pinfunction "1_1") (pintype "input"))
      (node (ref "R48") (pin "1") (pinfunction "1_1") (pintype "unspecified"))
      (node (ref "SW3") (pin "2") (pinfunction "2_2") (pintype "input"))
    )
    (net (code "46") (name "Net-(R49-Pad1)") (class "Default")
      (node (ref "R49") (pin "1") (pinfunction "1_1") (pintype "input"))
      (node (ref "R50") (pin "2") (pinfunction "2_2") (pintype "unspecified"))
      (node (ref "SW4") (pin "1") (pinfunction "1_1") (pintype "input"))
    )
    (net (code "47") (name "Net-(SW0-Pad3)") (class "Default")
      (node (ref "SW0") (pin "3") (pinfunction "3_3") (pintype "unspecified"))
      (node (ref "SW0") (pin "6") (pinfunction "6_6") (pintype "unspecified"))
      (node (ref "TYPE-C") (pin "A9") (pinfunction "VBUS_A9") (pintype "unspecified"))
      (node (ref "TYPE-C") (pin "B9") (pinfunction "VBUS_B9") (pintype "unspecified"))
    )
    (net (code "48") (name "Net-(U1-IO_L01N_2{slash}INIT_B)") (class "Default")
      (node (ref "R3") (pin "1") (pinfunction "1_1") (pintype "unspecified"))
      (node (ref "U1") (pin "25") (pinfunction "IO_L01N_2/INIT_B_25") (pintype "unspecified"))
      (node (ref "U2") (pin "8") (pinfunction "OE/RESET#_8") (pintype "unspecified"))
    )
    (net (code "49") (name "Net-(U1-IO_L07N_0{slash}HSWAP)") (class "Default")
      (node (ref "R6") (pin "1") (pinfunction "1_1") (pintype "unspecified"))
      (node (ref "U1") (pin "99") (pinfunction "IO_L07N_0/HSWAP_99") (pintype "unspecified"))
    )
    (net (code "50") (name "Net-(U1-IO_L07N_2{slash}DIN{slash}D0)") (class "Default")
      (node (ref "U1") (pin "44") (pinfunction "IO_L07N_2/DIN/D0_44") (pintype "unspecified"))
      (node (ref "U2") (pin "1") (pinfunction "D0_1") (pintype "unspecified"))
    )
    (net (code "51") (name "Net-(U1-IO_L09N_2{slash}CCLK)") (class "Default")
      (node (ref "U1") (pin "50") (pinfunction "IO_L09N_2/CCLK_50") (pintype "unspecified"))
      (node (ref "U2") (pin "3") (pinfunction "CLK_3") (pintype "unspecified"))
    )
    (net (code "52") (name "Net-(U1-PROG_B)") (class "Default")
      (node (ref "R2") (pin "1") (pinfunction "1_1") (pintype "unspecified"))
      (node (ref "U1") (pin "1") (pinfunction "PROG_B_1") (pintype "unspecified"))
      (node (ref "U2") (pin "7") (pinfunction "CF#_7") (pintype "unspecified"))
    )
    (net (code "53") (name "Net-(U3-A0#)") (class "Default")
      (node (ref "LOAD") (pin "1") (pinfunction "1_1") (pintype "unspecified"))
      (node (ref "LOAD") (pin "4") (pinfunction "4_4") (pintype "unspecified"))
      (node (ref "R1") (pin "2") (pinfunction "2_2") (pintype "unspecified"))
      (node (ref "U3") (pin "1") (pinfunction "A0#_1") (pintype "unspecified"))
      (node (ref "U3") (pin "10") (pinfunction "A3#_10") (pintype "unspecified"))
      (node (ref "U3") (pin "13") (pinfunction "A2#_13") (pintype "unspecified"))
      (node (ref "U3") (pin "4") (pinfunction "A1#_4") (pintype "unspecified"))
    )
    (net (code "54") (name "Net-(U3-B1)") (class "Default")
      (node (ref "R9") (pin "2") (pinfunction "2_2") (pintype "unspecified"))
      (node (ref "U3") (pin "5") (pinfunction "B1_5") (pintype "unspecified"))
    )
    (net (code "55") (name "Net-(U3-B2)") (class "Default")
      (node (ref "R7") (pin "1") (pinfunction "1_1") (pintype "unspecified"))
      (node (ref "U3") (pin "12") (pinfunction "B2_12") (pintype "unspecified"))
    )
    (net (code "56") (name "Net-(U3-B3)") (class "Default")
      (node (ref "R8") (pin "1") (pinfunction "1_1") (pintype "unspecified"))
      (node (ref "U3") (pin "9") (pinfunction "B3_9") (pintype "unspecified"))
    )
    (net (code "57") (name "Net-(U4-ADJ)") (class "Default")
      (node (ref "R13") (pin "2") (pinfunction "2_2") (pintype "input"))
      (node (ref "R14") (pin "2") (pinfunction "2_2") (pintype "input"))
      (node (ref "U4") (pin "1") (pinfunction "ADJ_1") (pintype "unspecified"))
    )
    (net (code "58") (name "Net-(U4-VIN)") (class "Default")
      (node (ref "C22") (pin "2") (pinfunction "2_2") (pintype "unspecified"))
      (node (ref "C24") (pin "1") (pinfunction "1_1") (pintype "input"))
      (node (ref "SW0") (pin "1") (pinfunction "1_1") (pintype "unspecified"))
      (node (ref "SW0") (pin "4") (pinfunction "4_4") (pintype "unspecified"))
      (node (ref "U4") (pin "3") (pinfunction "VIN_3") (pintype "unspecified"))
      (node (ref "U5") (pin "3") (pinfunction "VIN_3") (pintype "unspecified"))
      (node (ref "U6") (pin "3") (pinfunction "VIN_3") (pintype "unspecified"))
    )
    (net (code "59") (name "Net-(U5-ADJ)") (class "Default")
      (node (ref "R16") (pin "2") (pinfunction "2_2") (pintype "input"))
      (node (ref "R17") (pin "2") (pinfunction "2_2") (pintype "input"))
      (node (ref "U5") (pin "1") (pinfunction "ADJ_1") (pintype "unspecified"))
    )
    (net (code "60") (name "Net-(U7-1A)") (class "Default")
      (node (ref "C35") (pin "2") (pinfunction "2_2") (pintype "unspecified"))
      (node (ref "R43") (pin "2") (pinfunction "2_2") (pintype "unspecified"))
      (node (ref "U7") (pin "1") (pinfunction "1A_1") (pintype "unspecified"))
    )
    (net (code "61") (name "Net-(U7-2A)") (class "Default")
      (node (ref "C36") (pin "2") (pinfunction "2_2") (pintype "unspecified"))
      (node (ref "R45") (pin "2") (pinfunction "2_2") (pintype "unspecified"))
      (node (ref "U7") (pin "3") (pinfunction "2A_3") (pintype "unspecified"))
    )
    (net (code "62") (name "Net-(U7-3A)") (class "Default")
      (node (ref "C37") (pin "2") (pinfunction "2_2") (pintype "unspecified"))
      (node (ref "R48") (pin "2") (pinfunction "2_2") (pintype "unspecified"))
      (node (ref "U7") (pin "5") (pinfunction "3A_5") (pintype "unspecified"))
    )
    (net (code "63") (name "Net-(U7-4A)") (class "Default")
      (node (ref "C38") (pin "2") (pinfunction "2_2") (pintype "unspecified"))
      (node (ref "R50") (pin "1") (pinfunction "1_1") (pintype "unspecified"))
      (node (ref "U7") (pin "9") (pinfunction "4A_9") (pintype "unspecified"))
    )
    (net (code "64") (name "Net-(U7-5A)") (class "Default")
      (node (ref "R52") (pin "2") (pinfunction "2_2") (pintype "input"))
      (node (ref "U7") (pin "11") (pinfunction "5A_11") (pintype "unspecified"))
    )
    (net (code "65") (name "Net-(U7-6A)") (class "Default")
      (node (ref "R51") (pin "2") (pinfunction "2_2") (pintype "input"))
      (node (ref "U7") (pin "13") (pinfunction "6A_13") (pintype "unspecified"))
    )
    (net (code "66") (name "Net-(U8-DO)") (class "Default")
      (node (ref "R39") (pin "1") (pinfunction "1_1") (pintype "input"))
      (node (ref "R40") (pin "1") (pinfunction "1_1") (pintype "input"))
      (node (ref "U8") (pin "4") (pinfunction "DO_4") (pintype "unspecified"))
    )
    (net (code "67") (name "Net-(U10-3V3OUT)") (class "Default")
      (node (ref "C31") (pin "2") (pinfunction "2_2") (pintype "input"))
      (node (ref "U10") (pin "6") (pinfunction "3V3OUT_6") (pintype "output"))
    )
    (net (code "68") (name "Net-(U10-AVCC)") (class "Default")
      (node (ref "C30") (pin "1") (pinfunction "1_1") (pintype "unspecified"))
      (node (ref "R38") (pin "2") (pinfunction "2_2") (pintype "unspecified"))
      (node (ref "U10") (pin "46") (pinfunction "AVCC_46") (pintype "unspecified"))
    )
    (net (code "69") (name "Net-(U10-BDBUS2)") (class "Default")
      (node (ref "U10") (pin "37") (pinfunction "BDBUS3_37") (pintype "input"))
      (node (ref "U10") (pin "38") (pinfunction "BDBUS2_38") (pintype "output"))
    )
    (net (code "70") (name "Net-(U10-EECS)") (class "Default")
      (node (ref "U10") (pin "48") (pinfunction "EECS_48") (pintype "unspecified"))
      (node (ref "U8") (pin "1") (pinfunction "CS_1") (pintype "unspecified"))
    )
    (net (code "71") (name "Net-(U10-EEDATA)") (class "Default")
      (node (ref "R39") (pin "2") (pinfunction "2_2") (pintype "input"))
      (node (ref "U10") (pin "2") (pinfunction "EEDATA_2") (pintype "unspecified"))
      (node (ref "U8") (pin "3") (pinfunction "DI_3") (pintype "unspecified"))
    )
    (net (code "72") (name "Net-(U10-EESK)") (class "Default")
      (node (ref "U10") (pin "1") (pinfunction "EESK_1") (pintype "unspecified"))
      (node (ref "U8") (pin "2") (pinfunction "SK_2") (pintype "unspecified"))
    )
    (net (code "73") (name "Net-(U10-RSTOUT#)") (class "Default")
      (node (ref "R37") (pin "2") (pinfunction "2_2") (pintype "input"))
      (node (ref "U10") (pin "5") (pinfunction "RSTOUT#_5") (pintype "unspecified"))
    )
    (net (code "74") (name "Net-(U10-USBDM)") (class "Default")
      (node (ref "R35") (pin "2") (pinfunction "2_2") (pintype "input"))
      (node (ref "U10") (pin "8") (pinfunction "USBDM_8") (pintype "unspecified"))
    )
    (net (code "75") (name "Net-(U10-USBDP)") (class "Default")
      (node (ref "R36") (pin "2") (pinfunction "2_2") (pintype "input"))
      (node (ref "R37") (pin "1") (pinfunction "1_1") (pintype "input"))
      (node (ref "U10") (pin "7") (pinfunction "USBDP_7") (pintype "unspecified"))
    )
    (net (code "76") (name "Net-(U10-VCC1)") (class "Default")
      (node (ref "FB1") (pin "2") (pinfunction "2_2") (pintype "unspecified"))
      (node (ref "R38") (pin "1") (pinfunction "1_1") (pintype "unspecified"))
      (node (ref "U10") (pin "3") (pinfunction "VCC1_3") (pintype "passive"))
      (node (ref "U10") (pin "42") (pinfunction "VCC2_42") (pintype "passive"))
    )
    (net (code "77") (name "Net-(U10-XTIN)") (class "Default")
      (node (ref "C34") (pin "2") (pinfunction "2_2") (pintype "unspecified"))
      (node (ref "U10") (pin "43") (pinfunction "XTIN_43") (pintype "unspecified"))
      (node (ref "X3") (pin "1") (pinfunction "1_1") (pintype "input"))
    )
    (net (code "78") (name "Net-(U10-XTOUT)") (class "Default")
      (node (ref "C33") (pin "2") (pinfunction "2_2") (pintype "unspecified"))
      (node (ref "U10") (pin "44") (pinfunction "XTOUT_44") (pintype "unspecified"))
      (node (ref "X3") (pin "2") (pinfunction "2_2") (pintype "input"))
    )
    (net (code "79") (name "Net-(USB-D+)") (class "Default")
      (node (ref "R36") (pin "1") (pinfunction "1_1") (pintype "input"))
      (node (ref "USB") (pin "3") (pinfunction "D+_3") (pintype "unspecified"))
    )
    (net (code "80") (name "Net-(USB-D-)") (class "Default")
      (node (ref "R35") (pin "1") (pinfunction "1_1") (pintype "input"))
      (node (ref "USB") (pin "2") (pinfunction "D-_2") (pintype "unspecified"))
    )
    (net (code "81") (name "Net-(USB-VBUS)") (class "Default")
      (node (ref "C32") (pin "2") (pinfunction "2_2") (pintype "unspecified"))
      (node (ref "FB1") (pin "1") (pinfunction "1_1") (pintype "unspecified"))
      (node (ref "USB") (pin "1") (pinfunction "VBUS_1") (pintype "unspecified"))
    )
    (net (code "82") (name "Net-(X1-OUT)") (class "Default")
      (node (ref "R5") (pin "1") (pinfunction "1_1") (pintype "unspecified"))
      (node (ref "X1") (pin "3") (pinfunction "OUT_3") (pintype "unspecified"))
    )
    (net (code "83") (name "RESET") (class "Default")
      (node (ref "IC1") (pin "6") (pinfunction "OUT_6") (pintype "bidirectional"))
      (node (ref "R10") (pin "1") (pinfunction "1_1") (pintype "unspecified"))
      (node (ref "U1") (pin "85") (pinfunction "IO_L03P_0/GCLK6_85") (pintype "unspecified"))
    )
    (net (code "84") (name "RX") (class "Default")
      (node (ref "U1") (pin "70") (pinfunction "IO_L07P_1_70") (pintype "unspecified"))
      (node (ref "U10") (pin "40") (pinfunction "BDBUS0_40") (pintype "output"))
    )
    (net (code "85") (name "SW_1_IN") (class "Default")
      (node (ref "U1") (pin "22") (pinfunction "IO_L07P_3_22") (pintype "unspecified"))
      (node (ref "U7") (pin "2") (pinfunction "1Y_2") (pintype "unspecified"))
    )
    (net (code "86") (name "SW_2_IN") (class "Default")
      (node (ref "U1") (pin "23") (pinfunction "IO_L07N_3_23") (pintype "unspecified"))
      (node (ref "U7") (pin "4") (pinfunction "2Y_4") (pintype "unspecified"))
    )
    (net (code "87") (name "SW_3_IN") (class "Default")
      (node (ref "U1") (pin "24") (pinfunction "IO_L01P_2/CSO_B_24") (pintype "unspecified"))
      (node (ref "U7") (pin "6") (pinfunction "3Y_6") (pintype "unspecified"))
    )
    (net (code "88") (name "SW_4_IN") (class "Default")
      (node (ref "U1") (pin "26") (pinfunction "IO_L02P_2/DOUT/BUSY_26") (pintype "unspecified"))
      (node (ref "U7") (pin "8") (pinfunction "4Y_8") (pintype "unspecified"))
    )
    (net (code "89") (name "TCK") (class "Default")
      (node (ref "U1") (pin "77") (pinfunction "TCK_77") (pintype "unspecified"))
      (node (ref "U2") (pin "6") (pinfunction "TCK_6") (pintype "unspecified"))
      (node (ref "U3") (pin "8") (pinfunction "O3_8") (pintype "unspecified"))
    )
    (net (code "90") (name "TCK_FTDI") (class "Default")
      (node (ref "R8") (pin "2") (pinfunction "2_2") (pintype "unspecified"))
      (node (ref "U10") (pin "24") (pinfunction "ADBUS0_24") (pintype "unspecified"))
    )
    (net (code "91") (name "TDI") (class "Default")
      (node (ref "U2") (pin "4") (pinfunction "TDI_4") (pintype "unspecified"))
      (node (ref "U3") (pin "11") (pinfunction "O2_11") (pintype "unspecified"))
    )
    (net (code "92") (name "TDIO") (class "Default")
      (node (ref "U1") (pin "100") (pinfunction "TDI_100") (pintype "unspecified"))
      (node (ref "U2") (pin "17") (pinfunction "TDO_17") (pintype "unspecified"))
    )
    (net (code "93") (name "TDI_FTDI") (class "Default")
      (node (ref "R7") (pin "2") (pinfunction "2_2") (pintype "unspecified"))
      (node (ref "U10") (pin "23") (pinfunction "ADBUS1_23") (pintype "unspecified"))
    )
    (net (code "94") (name "TDO") (class "Default")
      (node (ref "U1") (pin "76") (pinfunction "TDO_76") (pintype "unspecified"))
      (node (ref "U3") (pin "2") (pinfunction "B0_2") (pintype "unspecified"))
    )
    (net (code "95") (name "TDO_FTDI") (class "Default")
      (node (ref "U10") (pin "22") (pinfunction "ADBUS2_22") (pintype "unspecified"))
      (node (ref "U3") (pin "3") (pinfunction "O0_3") (pintype "unspecified"))
    )
    (net (code "96") (name "TMS") (class "Default")
      (node (ref "U1") (pin "75") (pinfunction "TMS_75") (pintype "unspecified"))
      (node (ref "U2") (pin "5") (pinfunction "TMS_5") (pintype "unspecified"))
      (node (ref "U3") (pin "6") (pinfunction "O1_6") (pintype "unspecified"))
    )
    (net (code "97") (name "TMS_FTDI") (class "Default")
      (node (ref "R9") (pin "1") (pinfunction "1_1") (pintype "unspecified"))
      (node (ref "U10") (pin "21") (pinfunction "ADBUS3_21") (pintype "unspecified"))
    )
    (net (code "98") (name "TX") (class "Default")
      (node (ref "U1") (pin "71") (pinfunction "IO_L07N_1_71") (pintype "unspecified"))
      (node (ref "U10") (pin "39") (pinfunction "BDBUS1_39") (pintype "input"))
    )
    (net (code "99") (name "VCCAUX") (class "Default")
      (node (ref "C26") (pin "2") (pinfunction "2_2") (pintype "unspecified"))
      (node (ref "C27") (pin "1") (pinfunction "1_1") (pintype "input"))
      (node (ref "C5") (pin "2") (pinfunction "2_2") (pintype "unspecified"))
      (node (ref "C6") (pin "2") (pinfunction "2_2") (pintype "unspecified"))
      (node (ref "C7") (pin "2") (pinfunction "2_2") (pintype "unspecified"))
      (node (ref "C8") (pin "2") (pinfunction "2_2") (pintype "unspecified"))
      (node (ref "LOAD") (pin "3") (pinfunction "3_3") (pintype "unspecified"))
      (node (ref "LOAD") (pin "6") (pinfunction "6_6") (pintype "unspecified"))
      (node (ref "R16") (pin "1") (pinfunction "1_1") (pintype "input"))
      (node (ref "R2") (pin "2") (pinfunction "2_2") (pintype "unspecified"))
      (node (ref "R3") (pin "2") (pinfunction "2_2") (pintype "unspecified"))
      (node (ref "R4") (pin "1") (pinfunction "1_1") (pintype "unspecified"))
      (node (ref "R6") (pin "2") (pinfunction "2_2") (pintype "unspecified"))
      (node (ref "U1") (pin "21") (pinfunction "VCCAUX_21") (pintype "unspecified"))
      (node (ref "U1") (pin "46") (pinfunction "VCCAUX_46") (pintype "unspecified"))
      (node (ref "U1") (pin "74") (pinfunction "VCCAUX_74") (pintype "unspecified"))
      (node (ref "U1") (pin "96") (pinfunction "VCCAUX_96") (pintype "unspecified"))
      (node (ref "U2") (pin "19") (pinfunction "VCCO_19") (pintype "unspecified"))
      (node (ref "U2") (pin "20") (pinfunction "VCCJ_20") (pintype "unspecified"))
      (node (ref "U5") (pin "4") (pinfunction "OUT_4") (pintype "unspecified"))
    )
    (net (code "100") (name "VCCINT") (class "Default")
      (node (ref "C1") (pin "2") (pinfunction "2_2") (pintype "unspecified"))
      (node (ref "C2") (pin "2") (pinfunction "2_2") (pintype "unspecified"))
      (node (ref "C28") (pin "1") (pinfunction "1_1") (pintype "input"))
      (node (ref "C29") (pin "2") (pinfunction "2_2") (pintype "unspecified"))
      (node (ref "C3") (pin "2") (pinfunction "2_2") (pintype "unspecified"))
      (node (ref "C4") (pin "2") (pinfunction "2_2") (pintype "unspecified"))
      (node (ref "R19") (pin "1") (pinfunction "1_1") (pintype "input"))
      (node (ref "U1") (pin "28") (pinfunction "VCCINT_28") (pintype "unspecified"))
      (node (ref "U1") (pin "56") (pinfunction "VCCINT_56") (pintype "unspecified"))
      (node (ref "U1") (pin "6") (pinfunction "VCCINT_6") (pintype "unspecified"))
      (node (ref "U1") (pin "80") (pinfunction "VCCINT_80") (pintype "unspecified"))
      (node (ref "U6") (pin "4") (pinfunction "OUT_4") (pintype "unspecified"))
    )
    (net (code "101") (name "VCCO") (class "Default")
      (node (ref "7SEG1") (pin "3") (pinfunction "COM_3") (pintype "unspecified"))
      (node (ref "7SEG1") (pin "8") (pinfunction "COM_8") (pintype "unspecified"))
      (node (ref "7SEG2") (pin "3") (pinfunction "COM_3") (pintype "unspecified"))
      (node (ref "7SEG2") (pin "8") (pinfunction "COM_8") (pintype "unspecified"))
      (node (ref "C10") (pin "2") (pinfunction "2_2") (pintype "unspecified"))
      (node (ref "C11") (pin "2") (pinfunction "2_2") (pintype "unspecified"))
      (node (ref "C12") (pin "2") (pinfunction "2_2") (pintype "unspecified"))
      (node (ref "C13") (pin "2") (pinfunction "2_2") (pintype "unspecified"))
      (node (ref "C14") (pin "2") (pinfunction "2_2") (pintype "unspecified"))
      (node (ref "C15") (pin "2") (pinfunction "2_2") (pintype "unspecified"))
      (node (ref "C16") (pin "2") (pinfunction "2_2") (pintype "unspecified"))
      (node (ref "C23") (pin "2") (pinfunction "2_2") (pintype "unspecified"))
      (node (ref "C25") (pin "1") (pinfunction "1_1") (pintype "input"))
      (node (ref "C9") (pin "2") (pinfunction "2_2") (pintype "unspecified"))
      (node (ref "CN1") (pin "10") (pinfunction "10_10") (pintype "unspecified"))
      (node (ref "CN2") (pin "10") (pinfunction "10_10") (pintype "unspecified"))
      (node (ref "IC1") (pin "7") (pinfunction "VCCO_7") (pintype "bidirectional"))
      (node (ref "LED1") (pin "2") (pinfunction "+_2") (pintype "unspecified"))
      (node (ref "LED2") (pin "2") (pinfunction "+_2") (pintype "unspecified"))
      (node (ref "POWER") (pin "1") (pinfunction "+_1") (pintype "unspecified"))
      (node (ref "R10") (pin "2") (pinfunction "2_2") (pintype "unspecified"))
      (node (ref "R11") (pin "2") (pinfunction "2_2") (pintype "input"))
      (node (ref "R13") (pin "1") (pinfunction "1_1") (pintype "input"))
      (node (ref "R40") (pin "2") (pinfunction "2_2") (pintype "input"))
      (node (ref "R44") (pin "2") (pinfunction "2_2") (pintype "input"))
      (node (ref "R46") (pin "2") (pinfunction "2_2") (pintype "input"))
      (node (ref "R47") (pin "2") (pinfunction "2_2") (pintype "input"))
      (node (ref "R49") (pin "2") (pinfunction "2_2") (pintype "input"))
      (node (ref "U1") (pin "20") (pinfunction "VCCO_3_20") (pintype "unspecified"))
      (node (ref "U1") (pin "31") (pinfunction "VCCO_2_31") (pintype "unspecified"))
      (node (ref "U1") (pin "45") (pinfunction "VCCO_2_45") (pintype "unspecified"))
      (node (ref "U1") (pin "55") (pinfunction "VCCO_1_55") (pintype "unspecified"))
      (node (ref "U1") (pin "73") (pinfunction "VCCO_1_73") (pintype "unspecified"))
      (node (ref "U1") (pin "8") (pinfunction "VCCO_3_8") (pintype "unspecified"))
      (node (ref "U1") (pin "82") (pinfunction "VCCO_0_82") (pintype "unspecified"))
      (node (ref "U1") (pin "97") (pinfunction "VCCO_0_97") (pintype "unspecified"))
      (node (ref "U10") (pin "14") (pinfunction "VCCIOA_14") (pintype "passive"))
      (node (ref "U10") (pin "31") (pinfunction "VCCIOB_31") (pintype "unspecified"))
      (node (ref "U2") (pin "18") (pinfunction "VCCINT_18") (pintype "unspecified"))
      (node (ref "U3") (pin "14") (pinfunction "VCC_14") (pintype "unspecified"))
      (node (ref "U4") (pin "4") (pinfunction "OUT_4") (pintype "unspecified"))
      (node (ref "U7") (pin "14") (pinfunction "VCC_14") (pintype "unspecified"))
      (node (ref "U8") (pin "8") (pinfunction "VCC_8") (pintype "unspecified"))
      (node (ref "X1") (pin "4") (pinfunction "VCC_4") (pintype "unspecified"))
    )
    (net (code "102") (name "VPORT_1_1") (class "Default")
      (node (ref "CN1") (pin "1") (pinfunction "1_1") (pintype "unspecified"))
      (node (ref "U1") (pin "60") (pinfunction "IO_L03P_1/RHCLK0_60") (pintype "unspecified"))
    )
    (net (code "103") (name "VPORT_1_2") (class "Default")
      (node (ref "CN1") (pin "2") (pinfunction "2_2") (pintype "unspecified"))
      (node (ref "U1") (pin "61") (pinfunction "IO_L03N_1/RHCLK1_61") (pintype "unspecified"))
    )
    (net (code "104") (name "VPORT_1_3") (class "Default")
      (node (ref "CN1") (pin "3") (pinfunction "3_3") (pintype "unspecified"))
      (node (ref "U1") (pin "62") (pinfunction "IO_L04P_1/RHCLK2_62") (pintype "unspecified"))
    )
    (net (code "105") (name "VPORT_1_4") (class "Default")
      (node (ref "CN1") (pin "4") (pinfunction "4_4") (pintype "unspecified"))
      (node (ref "U1") (pin "63") (pinfunction "IO_L04N_1/RHCLK3_63") (pintype "unspecified"))
    )
    (net (code "106") (name "VPORT_1_5") (class "Default")
      (node (ref "CN1") (pin "5") (pinfunction "5_5") (pintype "unspecified"))
      (node (ref "U1") (pin "65") (pinfunction "IO_L05P_1/RHCLK4_65") (pintype "unspecified"))
    )
    (net (code "107") (name "VPORT_1_6") (class "Default")
      (node (ref "CN1") (pin "6") (pinfunction "6_6") (pintype "unspecified"))
      (node (ref "U1") (pin "66") (pinfunction "IO_L05N_1/RHCLK5_66") (pintype "unspecified"))
    )
    (net (code "108") (name "VPORT_1_7") (class "Default")
      (node (ref "CN1") (pin "7") (pinfunction "7_7") (pintype "unspecified"))
      (node (ref "U1") (pin "67") (pinfunction "IO_L06P_1/RHCLK6_67") (pintype "unspecified"))
    )
    (net (code "109") (name "VPORT_1_8") (class "Default")
      (node (ref "CN1") (pin "8") (pinfunction "8_8") (pintype "unspecified"))
      (node (ref "U1") (pin "68") (pinfunction "IO_L06N_1/RHCLK7_68") (pintype "unspecified"))
    )
    (net (code "110") (name "VPORT_2_1") (class "Default")
      (node (ref "CN2") (pin "1") (pinfunction "1_1") (pintype "unspecified"))
      (node (ref "U1") (pin "33") (pinfunction "IO_L03N_2/D6/GCLK13_33") (pintype "unspecified"))
    )
    (net (code "111") (name "VPORT_2_2") (class "Default")
      (node (ref "CN2") (pin "2") (pinfunction "2_2") (pintype "unspecified"))
      (node (ref "U1") (pin "34") (pinfunction "IO/D5_34") (pintype "unspecified"))
    )
    (net (code "112") (name "VPORT_2_3") (class "Default")
      (node (ref "CN2") (pin "3") (pinfunction "3_3") (pintype "unspecified"))
      (node (ref "U1") (pin "35") (pinfunction "IO_L04P_2/D4/GCLK14_35") (pintype "unspecified"))
    )
    (net (code "113") (name "VPORT_2_4") (class "Default")
      (node (ref "CN2") (pin "4") (pinfunction "4_4") (pintype "unspecified"))
      (node (ref "U1") (pin "36") (pinfunction "IO_L04N_2/D3/GCLK15_36") (pintype "unspecified"))
    )
    (net (code "114") (name "VPORT_2_5") (class "Default")
      (node (ref "CN2") (pin "5") (pinfunction "5_5") (pintype "unspecified"))
      (node (ref "U1") (pin "40") (pinfunction "IO_L06P_2/D2/GCLK2_40") (pintype "unspecified"))
    )
    (net (code "115") (name "VPORT_2_6") (class "Default")
      (node (ref "CN2") (pin "6") (pinfunction "6_6") (pintype "unspecified"))
      (node (ref "U1") (pin "41") (pinfunction "IO_L06N_2/D1/GCLK3_41") (pintype "unspecified"))
    )
    (net (code "116") (name "VPORT_2_7") (class "Default")
      (node (ref "CN2") (pin "7") (pinfunction "7_7") (pintype "unspecified"))
      (node (ref "U1") (pin "57") (pinfunction "IO_L02P_1_57") (pintype "unspecified"))
    )
    (net (code "117") (name "VPORT_2_8") (class "Default")
      (node (ref "CN2") (pin "8") (pinfunction "8_8") (pintype "unspecified"))
      (node (ref "U1") (pin "58") (pinfunction "IO_L02N_1_58") (pintype "unspecified"))
    )
    (net (code "118") (name "unconnected-(IC1-NC-Pad1)") (class "Default")
      (node (ref "IC1") (pin "1") (pinfunction "NC_1") (pintype "bidirectional+no_connect"))
    )
    (net (code "119") (name "unconnected-(IC1-NC-Pad3)") (class "Default")
      (node (ref "IC1") (pin "3") (pinfunction "NC_3") (pintype "bidirectional+no_connect"))
    )
    (net (code "120") (name "unconnected-(IC1-NC-Pad8)") (class "Default")
      (node (ref "IC1") (pin "8") (pinfunction "NC_8") (pintype "bidirectional+no_connect"))
    )
    (net (code "121") (name "unconnected-(LOAD-Pad2)") (class "Default")
      (node (ref "LOAD") (pin "2") (pinfunction "2_2") (pintype "unspecified+no_connect"))
    )
    (net (code "122") (name "unconnected-(LOAD-Pad5)") (class "Default")
      (node (ref "LOAD") (pin "5") (pinfunction "5_5") (pintype "unspecified+no_connect"))
    )
    (net (code "123") (name "unconnected-(SW0-Pad2)") (class "Default")
      (node (ref "SW0") (pin "2") (pinfunction "2_2") (pintype "unspecified+no_connect"))
    )
    (net (code "124") (name "unconnected-(SW0-Pad5)") (class "Default")
      (node (ref "SW0") (pin "5") (pinfunction "5_5") (pintype "unspecified+no_connect"))
    )
    (net (code "125") (name "unconnected-(TYPE-C-CC1-PadA5)") (class "Default")
      (node (ref "TYPE-C") (pin "A5") (pinfunction "CC1_A5") (pintype "unspecified+no_connect"))
    )
    (net (code "126") (name "unconnected-(TYPE-C-CC2-PadB5)") (class "Default")
      (node (ref "TYPE-C") (pin "B5") (pinfunction "CC2_B5") (pintype "unspecified+no_connect"))
    )
    (net (code "127") (name "unconnected-(U1-IO_L01N_0-Pad79)") (class "Default")
      (node (ref "U1") (pin "79") (pinfunction "IO_L01N_0_79") (pintype "unspecified+no_connect"))
    )
    (net (code "128") (name "unconnected-(U1-IO_L01P_0-Pad78)") (class "Default")
      (node (ref "U1") (pin "78") (pinfunction "IO_L01P_0_78") (pintype "unspecified+no_connect"))
    )
    (net (code "129") (name "unconnected-(U1-IO_L02N_0{slash}GCLK5-Pad84)") (class "Default")
      (node (ref "U1") (pin "84") (pinfunction "IO_L02N_0/GCLK5_84") (pintype "unspecified+no_connect"))
    )
    (net (code "130") (name "unconnected-(U1-IO_L02N_2{slash}MOSI{slash}CSI_B-Pad27)") (class "Default")
      (node (ref "U1") (pin "27") (pinfunction "IO_L02N_2/MOSI/CSI_B_27") (pintype "unspecified+no_connect"))
    )
    (net (code "131") (name "unconnected-(U1-IO_L03P_2{slash}D7{slash}GCLK12-Pad32)") (class "Default")
      (node (ref "U1") (pin "32") (pinfunction "IO_L03P_2/D7/GCLK12_32") (pintype "unspecified+no_connect"))
    )
    (net (code "132") (name "unconnected-(U1-IO_L06N_3{slash}LHCLK7-Pad18)") (class "Default")
      (node (ref "U1") (pin "18") (pinfunction "IO_L06N_3/LHCLK7_18") (pintype "unspecified+no_connect"))
    )
    (net (code "133") (name "unconnected-(U1-IO_L06P_3{slash}LHCLK6-Pad17)") (class "Default")
      (node (ref "U1") (pin "17") (pinfunction "IO_L06P_3/LHCLK6_17") (pintype "unspecified+no_connect"))
    )
    (net (code "134") (name "unconnected-(U1-IO_L07P_0-Pad98)") (class "Default")
      (node (ref "U1") (pin "98") (pinfunction "IO_L07P_0_98") (pintype "unspecified+no_connect"))
    )
    (net (code "135") (name "unconnected-(U1-IO_L08P_2{slash}VS2-Pad47)") (class "Default")
      (node (ref "U1") (pin "47") (pinfunction "IO_L08P_2/VS2_47") (pintype "unspecified+no_connect"))
    )
    (net (code "136") (name "unconnected-(U1-IO_L09P_2{slash}VS0-Pad49)") (class "Default")
      (node (ref "U1") (pin "49") (pinfunction "IO_L09P_2/VS0_49") (pintype "unspecified+no_connect"))
    )
    (net (code "137") (name "unconnected-(U1-IP-Pad13)") (class "Default")
      (node (ref "U1") (pin "13") (pinfunction "IP_13") (pintype "unspecified+no_connect"))
    )
    (net (code "138") (name "unconnected-(U1-IP_L04N_0{slash}GCLK9-Pad89)") (class "Default")
      (node (ref "U1") (pin "89") (pinfunction "IP_L04N_0/GCLK9_89") (pintype "unspecified+no_connect"))
    )
    (net (code "139") (name "unconnected-(U1-IP_L04P_0{slash}GCLK8-Pad88)") (class "Default")
      (node (ref "U1") (pin "88") (pinfunction "IP_L04P_0/GCLK8_88") (pintype "unspecified+no_connect"))
    )
    (net (code "140") (name "unconnected-(U1-IP_L05P_2{slash}RDWR_B{slash}GCLK0-Pad38)") (class "Default")
      (node (ref "U1") (pin "38") (pinfunction "IP_L05P_2/RDWR_B/GCLK0_38") (pintype "unspecified+no_connect"))
    )
    (net (code "141") (name "unconnected-(U1-IP{slash}VREF_1-Pad69)") (class "Default")
      (node (ref "U1") (pin "69") (pinfunction "IP/VREF_1_69") (pintype "unspecified+no_connect"))
    )
    (net (code "142") (name "unconnected-(U1-IP{slash}VREF_2-Pad30)") (class "Default")
      (node (ref "U1") (pin "30") (pinfunction "IP/VREF_2_30") (pintype "unspecified+no_connect"))
    )
    (net (code "143") (name "unconnected-(U1-O_L08N_2{slash}VS1-Pad48)") (class "Default")
      (node (ref "U1") (pin "48") (pinfunction "O_L08N_2/VS1_48") (pintype "unspecified+no_connect"))
    )
    (net (code "144") (name "unconnected-(U2-CEO#-Pad13)") (class "Default")
      (node (ref "U2") (pin "13") (pinfunction "CEO#_13") (pintype "unspecified+no_connect"))
    )
    (net (code "145") (name "unconnected-(U2-DNC-Pad2)") (class "Default")
      (node (ref "U2") (pin "2") (pinfunction "DNC_2") (pintype "unspecified+no_connect"))
    )
    (net (code "146") (name "unconnected-(U2-DNC-Pad9)") (class "Default")
      (node (ref "U2") (pin "9") (pinfunction "DNC_9") (pintype "unspecified+no_connect"))
    )
    (net (code "147") (name "unconnected-(U2-DNC-Pad12)") (class "Default")
      (node (ref "U2") (pin "12") (pinfunction "DNC_12") (pintype "unspecified+no_connect"))
    )
    (net (code "148") (name "unconnected-(U2-DNC-Pad14)") (class "Default")
      (node (ref "U2") (pin "14") (pinfunction "DNC_14") (pintype "unspecified+no_connect"))
    )
    (net (code "149") (name "unconnected-(U2-DNC-Pad15)") (class "Default")
      (node (ref "U2") (pin "15") (pinfunction "DNC_15") (pintype "unspecified+no_connect"))
    )
    (net (code "150") (name "unconnected-(U2-DNC-Pad16)") (class "Default")
      (node (ref "U2") (pin "16") (pinfunction "DNC_16") (pintype "unspecified+no_connect"))
    )
    (net (code "151") (name "unconnected-(U7-5Y-Pad10)") (class "Default")
      (node (ref "U7") (pin "10") (pinfunction "5Y_10") (pintype "unspecified+no_connect"))
    )
    (net (code "152") (name "unconnected-(U7-6Y-Pad12)") (class "Default")
      (node (ref "U7") (pin "12") (pinfunction "6Y_12") (pintype "unspecified+no_connect"))
    )
    (net (code "153") (name "unconnected-(U8-NC-Pad6)") (class "Default")
      (node (ref "U8") (pin "6") (pinfunction "NC_6") (pintype "unspecified+no_connect"))
    )
    (net (code "154") (name "unconnected-(U8-NC-Pad7)") (class "Default")
      (node (ref "U8") (pin "7") (pinfunction "NC_7") (pintype "unspecified+no_connect"))
    )
    (net (code "155") (name "unconnected-(U10-ACBUS0-Pad15)") (class "Default")
      (node (ref "U10") (pin "15") (pinfunction "ACBUS0_15") (pintype "unspecified+no_connect"))
    )
    (net (code "156") (name "unconnected-(U10-ACBUS1-Pad13)") (class "Default")
      (node (ref "U10") (pin "13") (pinfunction "ACBUS1_13") (pintype "unspecified+no_connect"))
    )
    (net (code "157") (name "unconnected-(U10-ACBUS2-Pad12)") (class "Default")
      (node (ref "U10") (pin "12") (pinfunction "ACBUS2_12") (pintype "unspecified+no_connect"))
    )
    (net (code "158") (name "unconnected-(U10-ACBUS3-Pad11)") (class "Default")
      (node (ref "U10") (pin "11") (pinfunction "ACBUS3_11") (pintype "unspecified+no_connect"))
    )
    (net (code "159") (name "unconnected-(U10-ADBUS4-Pad20)") (class "Default")
      (node (ref "U10") (pin "20") (pinfunction "ADBUS4_20") (pintype "unspecified+no_connect"))
    )
    (net (code "160") (name "unconnected-(U10-ADBUS5-Pad19)") (class "Default")
      (node (ref "U10") (pin "19") (pinfunction "ADBUS5_19") (pintype "unspecified+no_connect"))
    )
    (net (code "161") (name "unconnected-(U10-ADBUS6-Pad17)") (class "Default")
      (node (ref "U10") (pin "17") (pinfunction "ADBUS6_17") (pintype "unspecified+no_connect"))
    )
    (net (code "162") (name "unconnected-(U10-ADBUS7-Pad16)") (class "Default")
      (node (ref "U10") (pin "16") (pinfunction "ADBUS7_16") (pintype "unspecified+no_connect"))
    )
    (net (code "163") (name "unconnected-(U10-BCBUS0-Pad30)") (class "Default")
      (node (ref "U10") (pin "30") (pinfunction "BCBUS0_30") (pintype "unspecified+no_connect"))
    )
    (net (code "164") (name "unconnected-(U10-BCBUS1-Pad29)") (class "Default")
      (node (ref "U10") (pin "29") (pinfunction "BCBUS1_29") (pintype "unspecified+no_connect"))
    )
    (net (code "165") (name "unconnected-(U10-BCBUS2-Pad28)") (class "Default")
      (node (ref "U10") (pin "28") (pinfunction "BCBUS2_28") (pintype "unspecified+no_connect"))
    )
    (net (code "166") (name "unconnected-(U10-BCBUS3-Pad27)") (class "Default")
      (node (ref "U10") (pin "27") (pinfunction "BCBUS3_27") (pintype "unspecified+no_connect"))
    )
    (net (code "167") (name "unconnected-(U10-BDBUS4-Pad36)") (class "Default")
      (node (ref "U10") (pin "36") (pinfunction "BDBUS4_36") (pintype "output+no_connect"))
    )
    (net (code "168") (name "unconnected-(U10-BDBUS5-Pad35)") (class "Default")
      (node (ref "U10") (pin "35") (pinfunction "BDBUS5_35") (pintype "input+no_connect"))
    )
    (net (code "169") (name "unconnected-(U10-BDBUS6-Pad33)") (class "Default")
      (node (ref "U10") (pin "33") (pinfunction "BDBUS6_33") (pintype "input+no_connect"))
    )
    (net (code "170") (name "unconnected-(U10-BDBUS7-Pad32)") (class "Default")
      (node (ref "U10") (pin "32") (pinfunction "BDBUS7_32") (pintype "input+no_connect"))
    )
    (net (code "171") (name "unconnected-(U10-PWEN#-Pad41)") (class "Default")
      (node (ref "U10") (pin "41") (pinfunction "PWEN#_41") (pintype "unspecified+no_connect"))
    )
    (net (code "172") (name "unconnected-(U10-RESET#-Pad4)") (class "Default")
      (node (ref "U10") (pin "4") (pinfunction "RESET#_4") (pintype "unspecified+no_connect"))
    )
    (net (code "173") (name "unconnected-(U10-SIWUA-Pad10)") (class "Default")
      (node (ref "U10") (pin "10") (pinfunction "SIWUA_10") (pintype "unspecified+no_connect"))
    )
    (net (code "174") (name "unconnected-(U10-SIWUB-Pad26)") (class "Default")
      (node (ref "U10") (pin "26") (pinfunction "SIWUB_26") (pintype "unspecified+no_connect"))
    )
    (net (code "175") (name "unconnected-(USB-ID-Pad4)") (class "Default")
      (node (ref "USB") (pin "4") (pinfunction "ID_4") (pintype "unspecified+no_connect"))
    )
    (net (code "176") (name "unconnected-(X1-OE{slash}ST-Pad1)") (class "Default")
      (node (ref "X1") (pin "1") (pinfunction "OE/ST_1") (pintype "unspecified+no_connect"))
    )
  )
)
